# out_role.net
KiCad netlist of a schematic drawn in Altium Designer
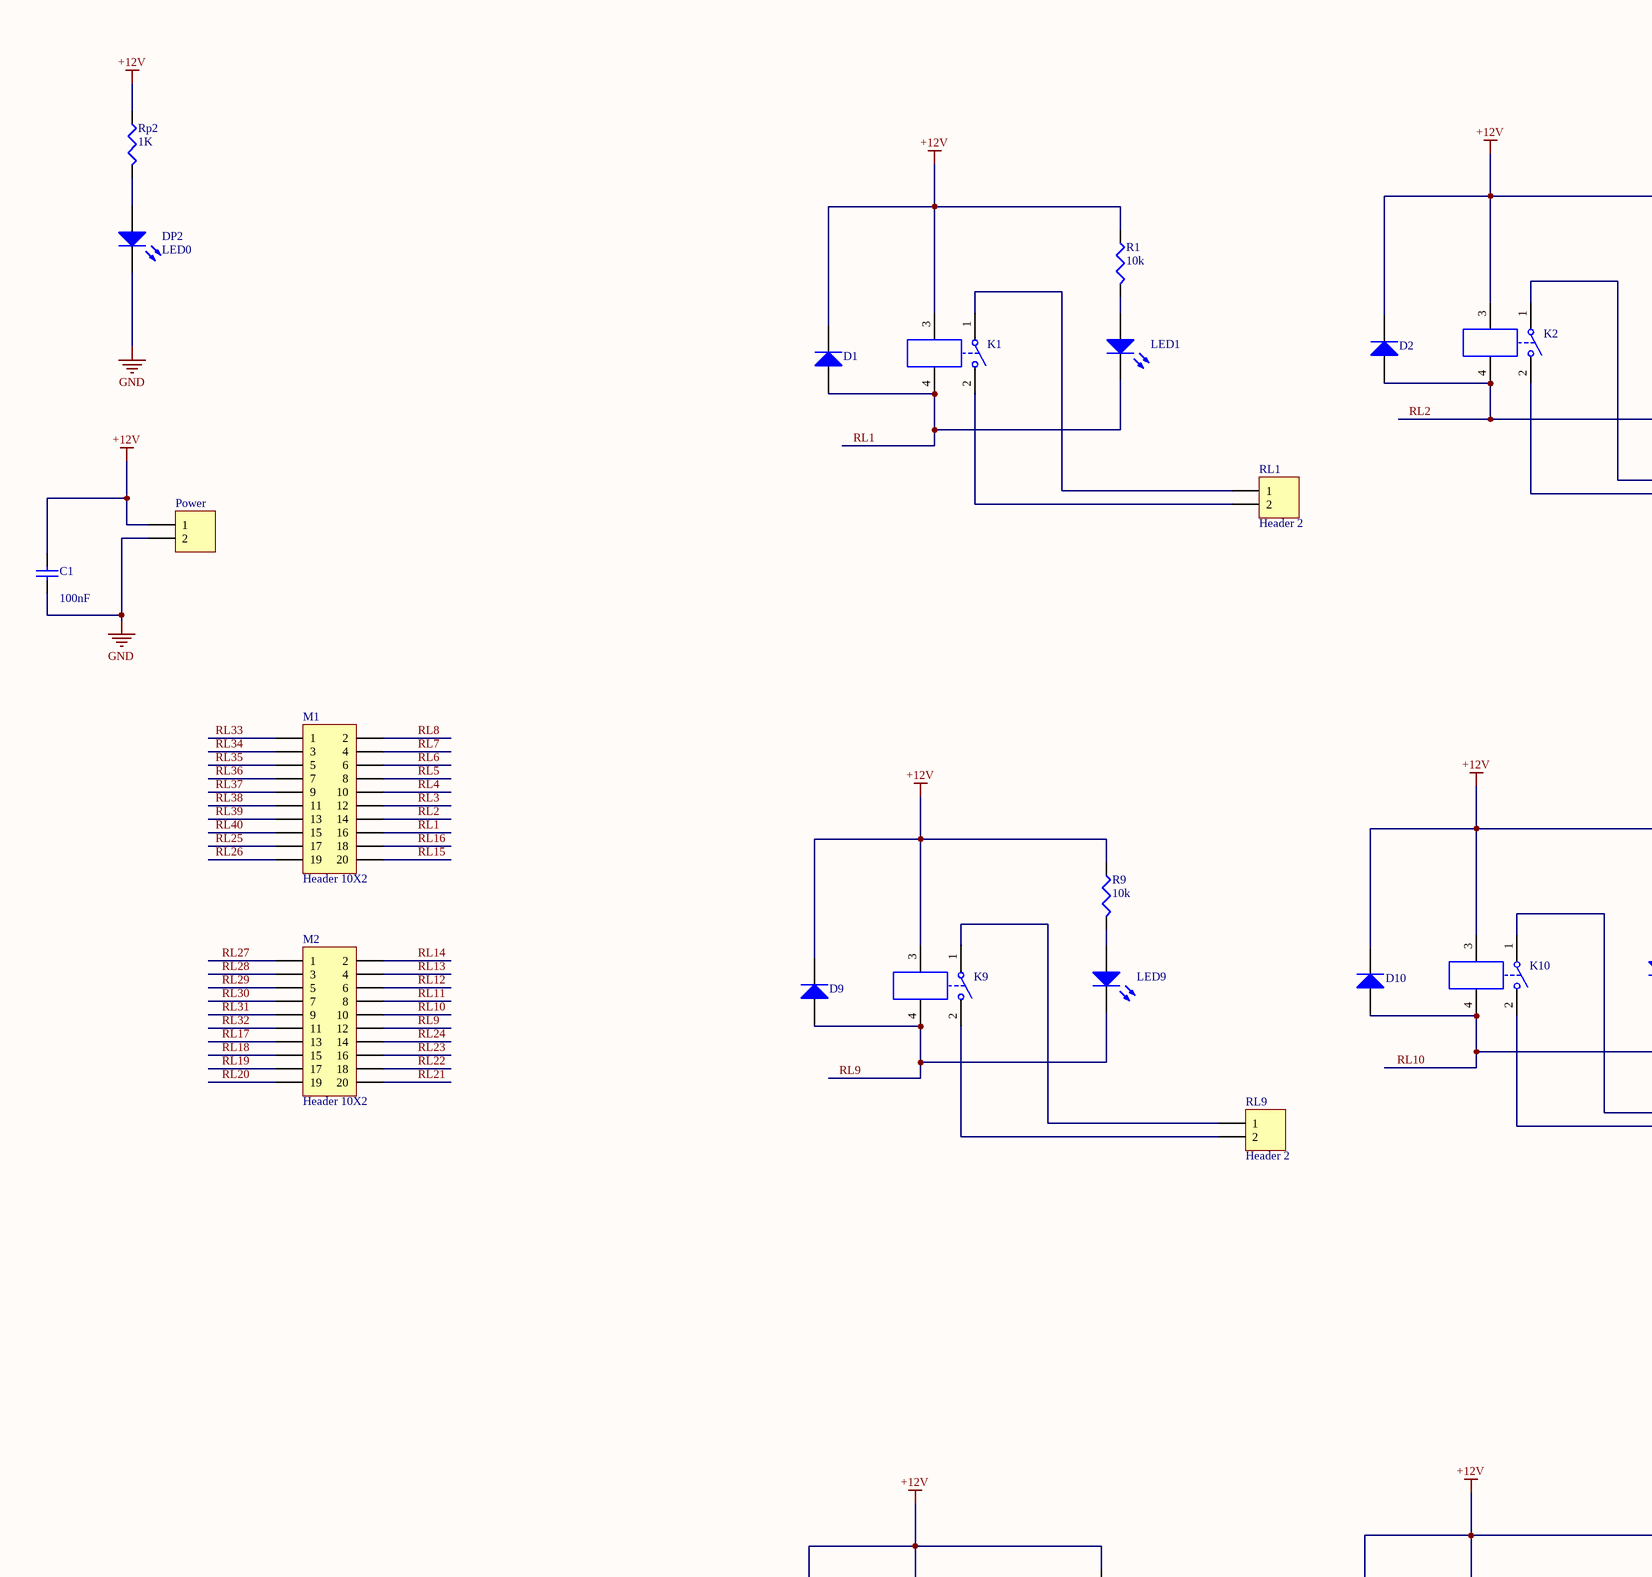
[diagram p0: out_role.SchDoc, top left]
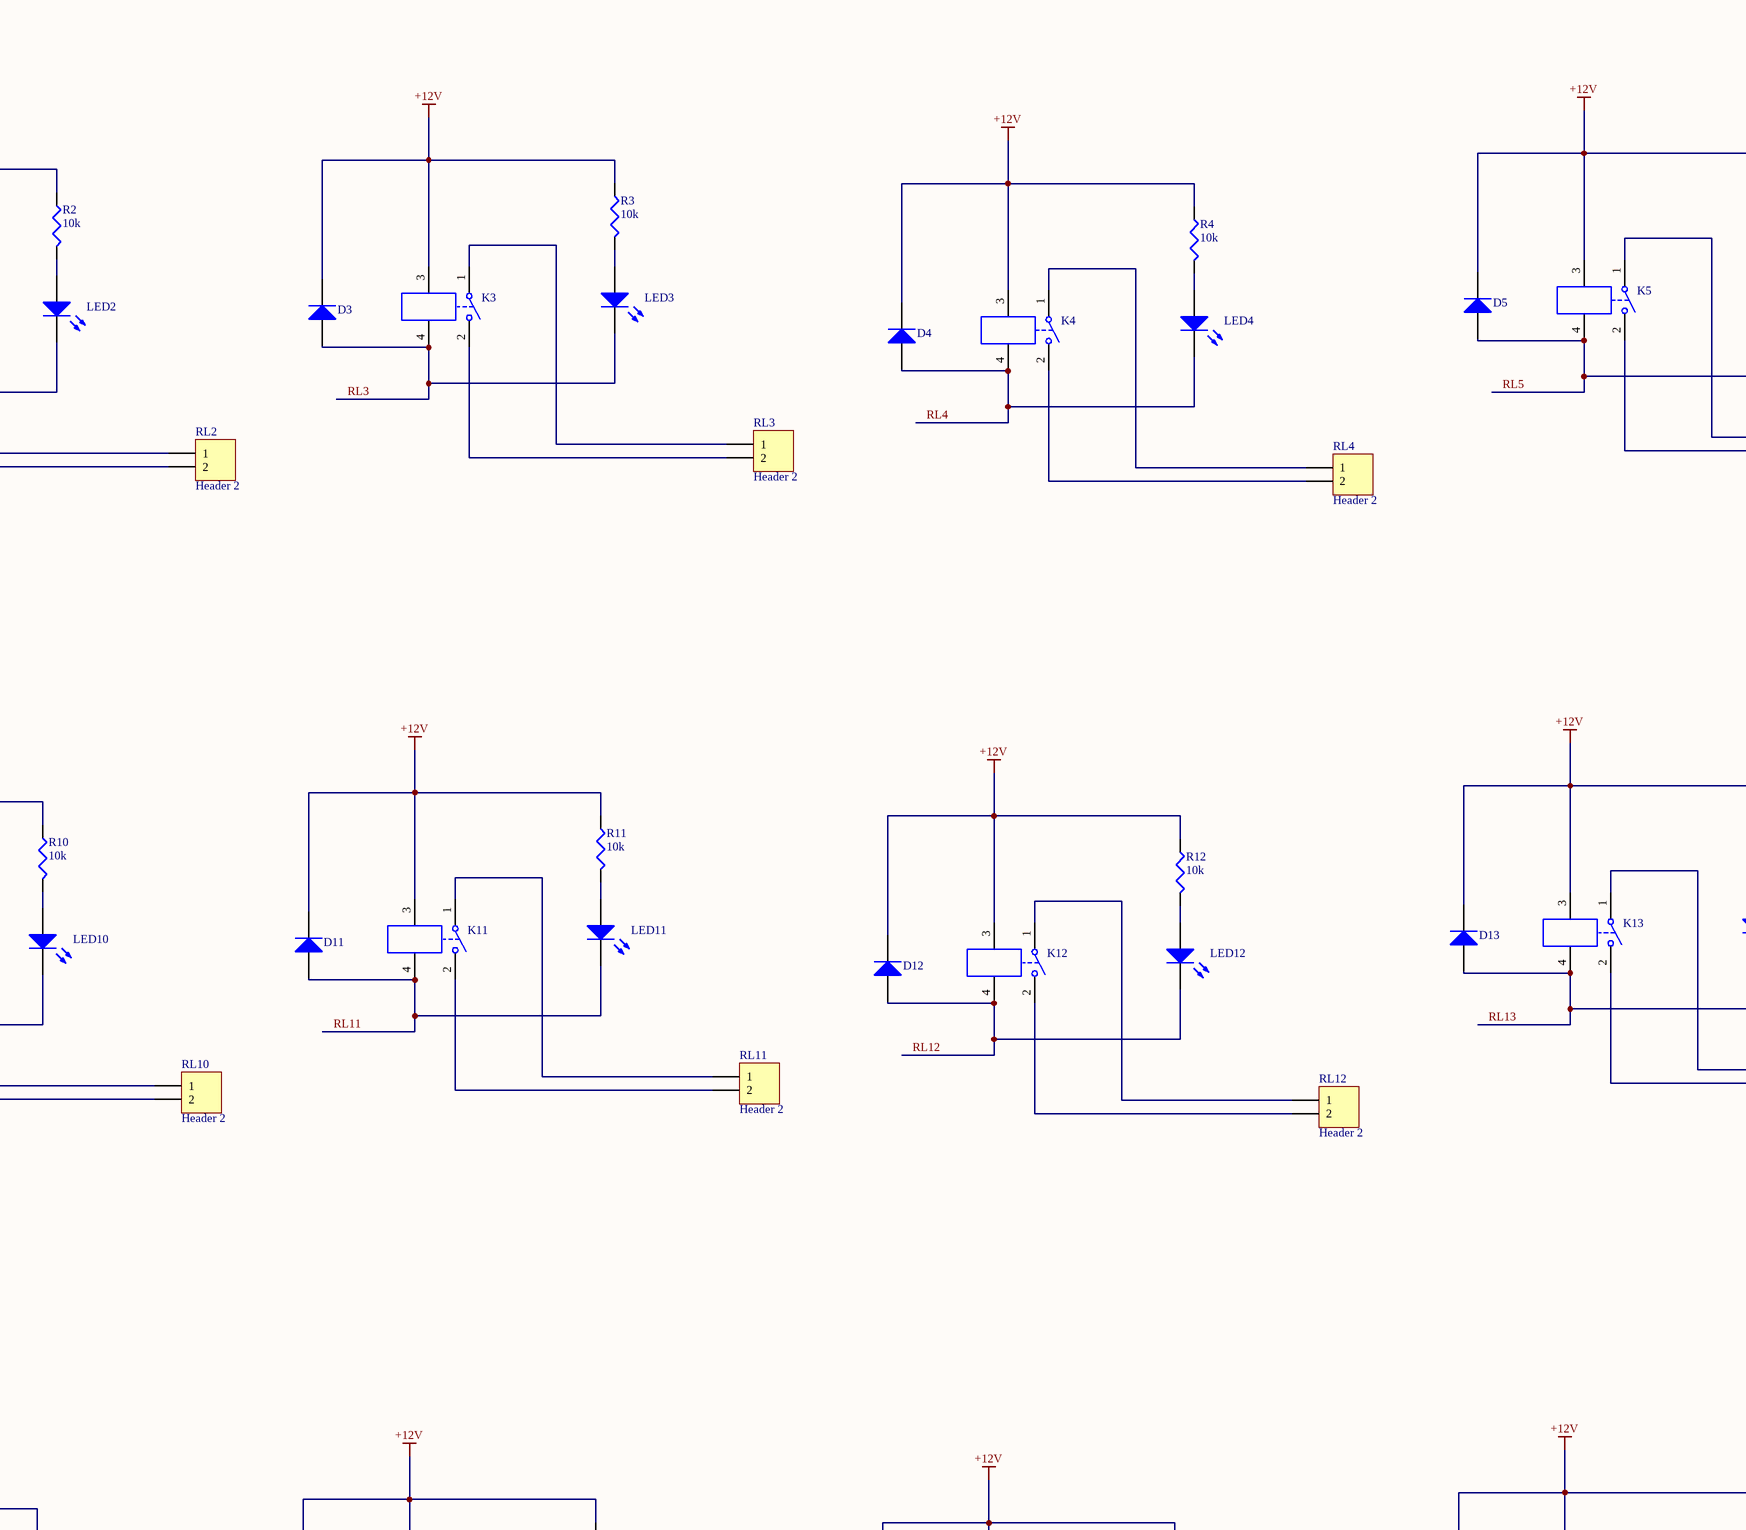
[diagram p1: out_role.SchDoc, top middle]
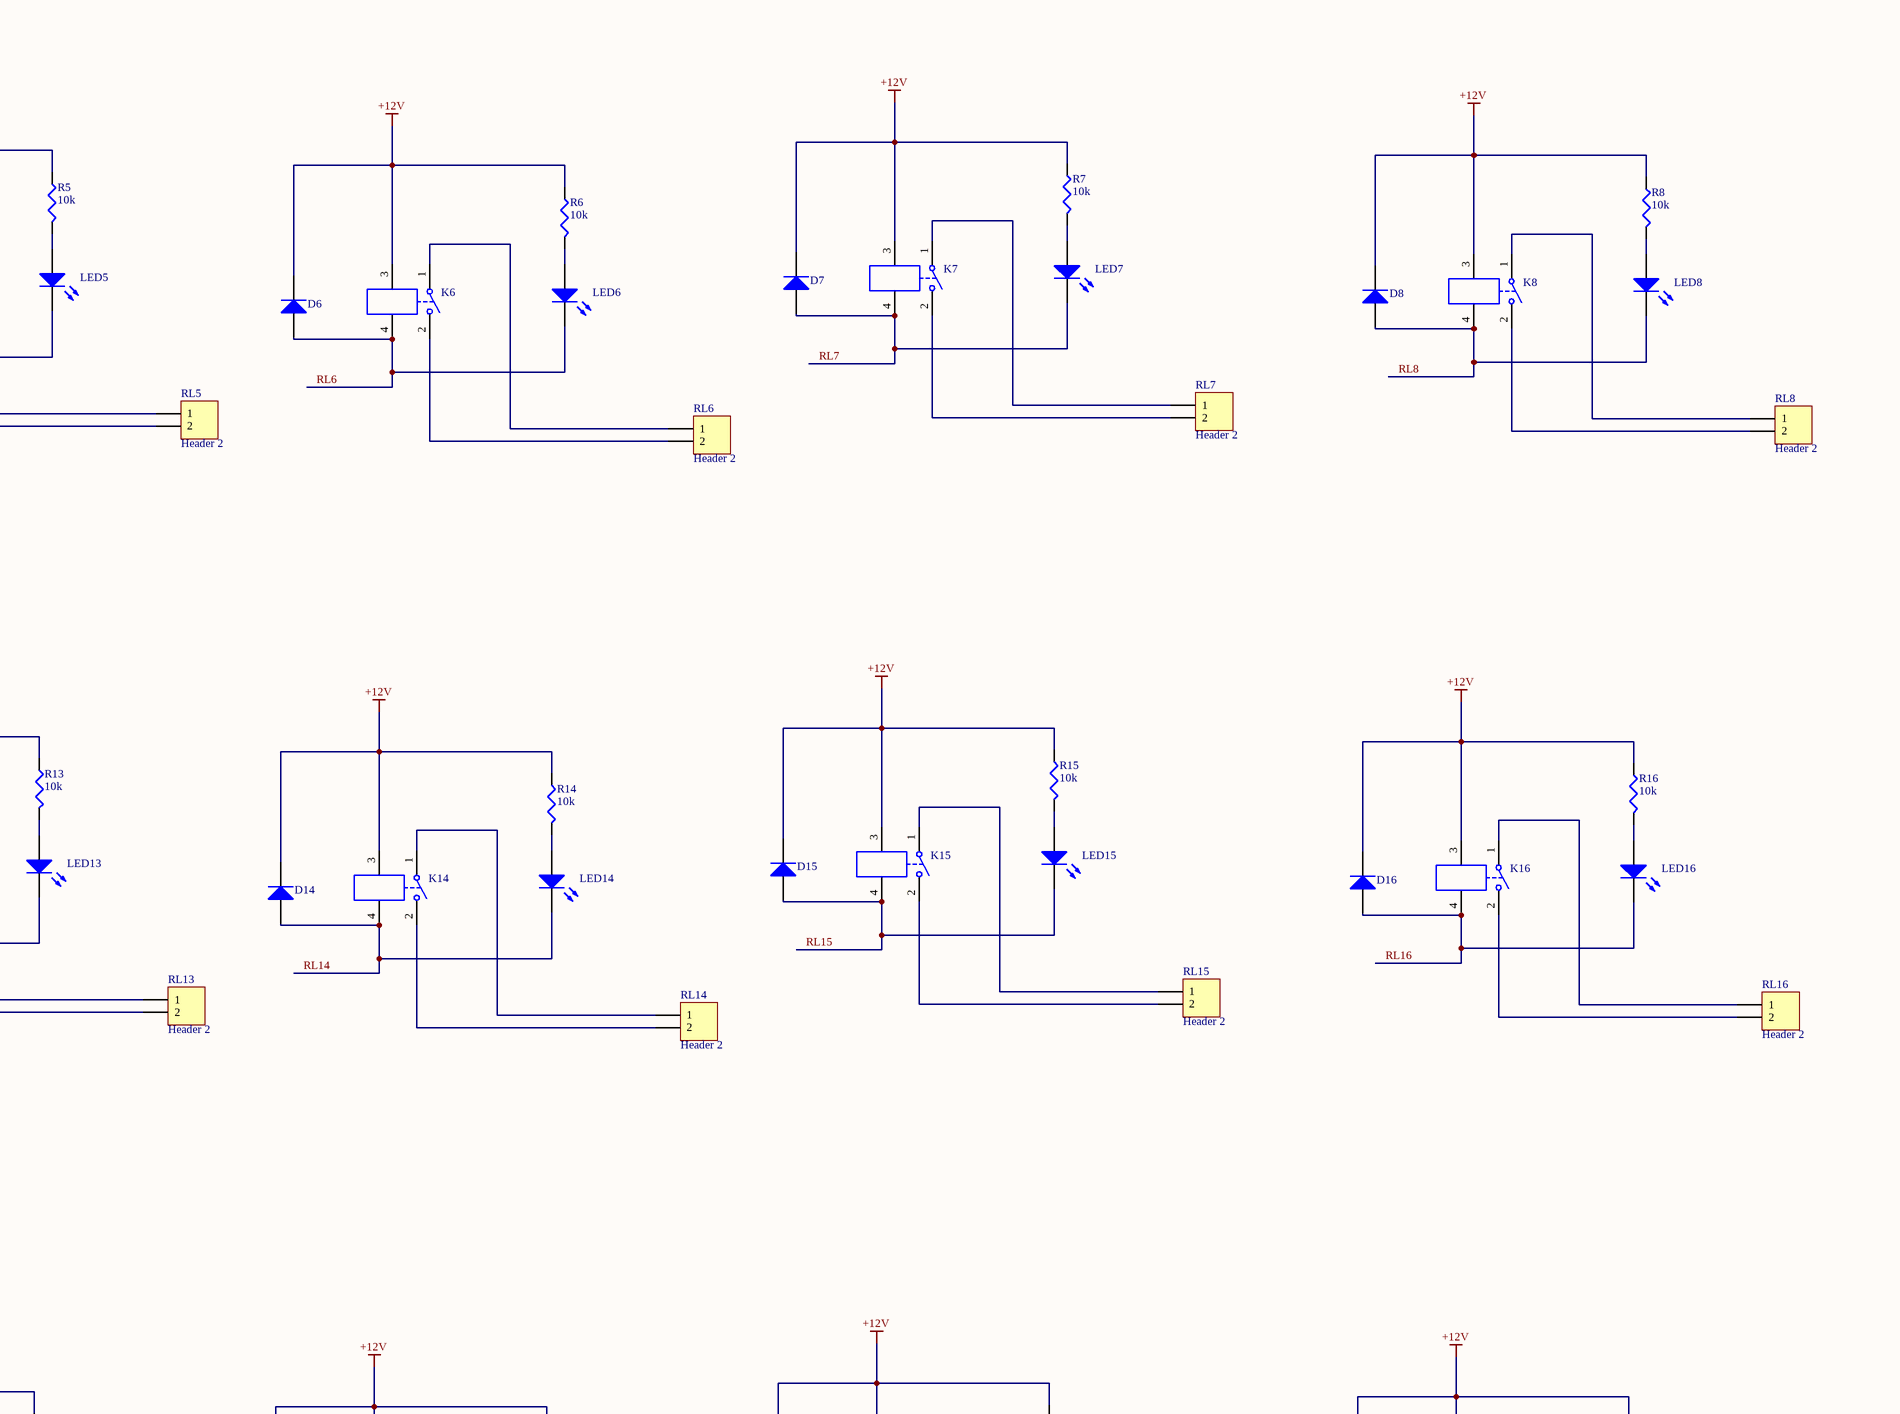
[diagram p2: out_role.SchDoc, top right]
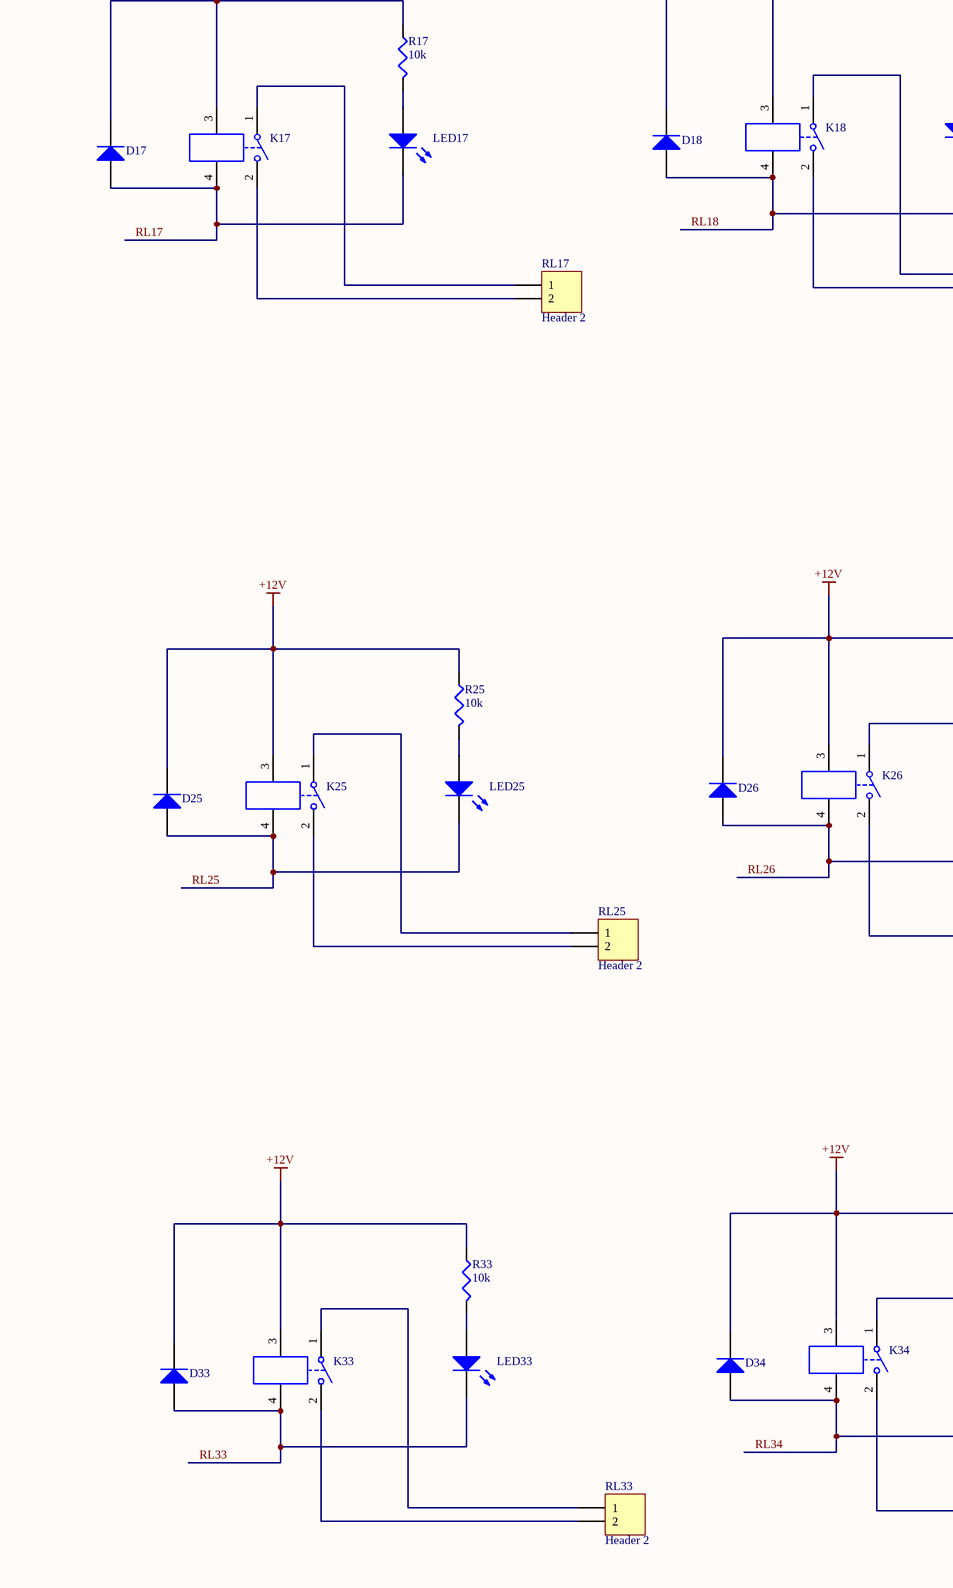
[diagram p3: out_role.SchDoc, bottom left]
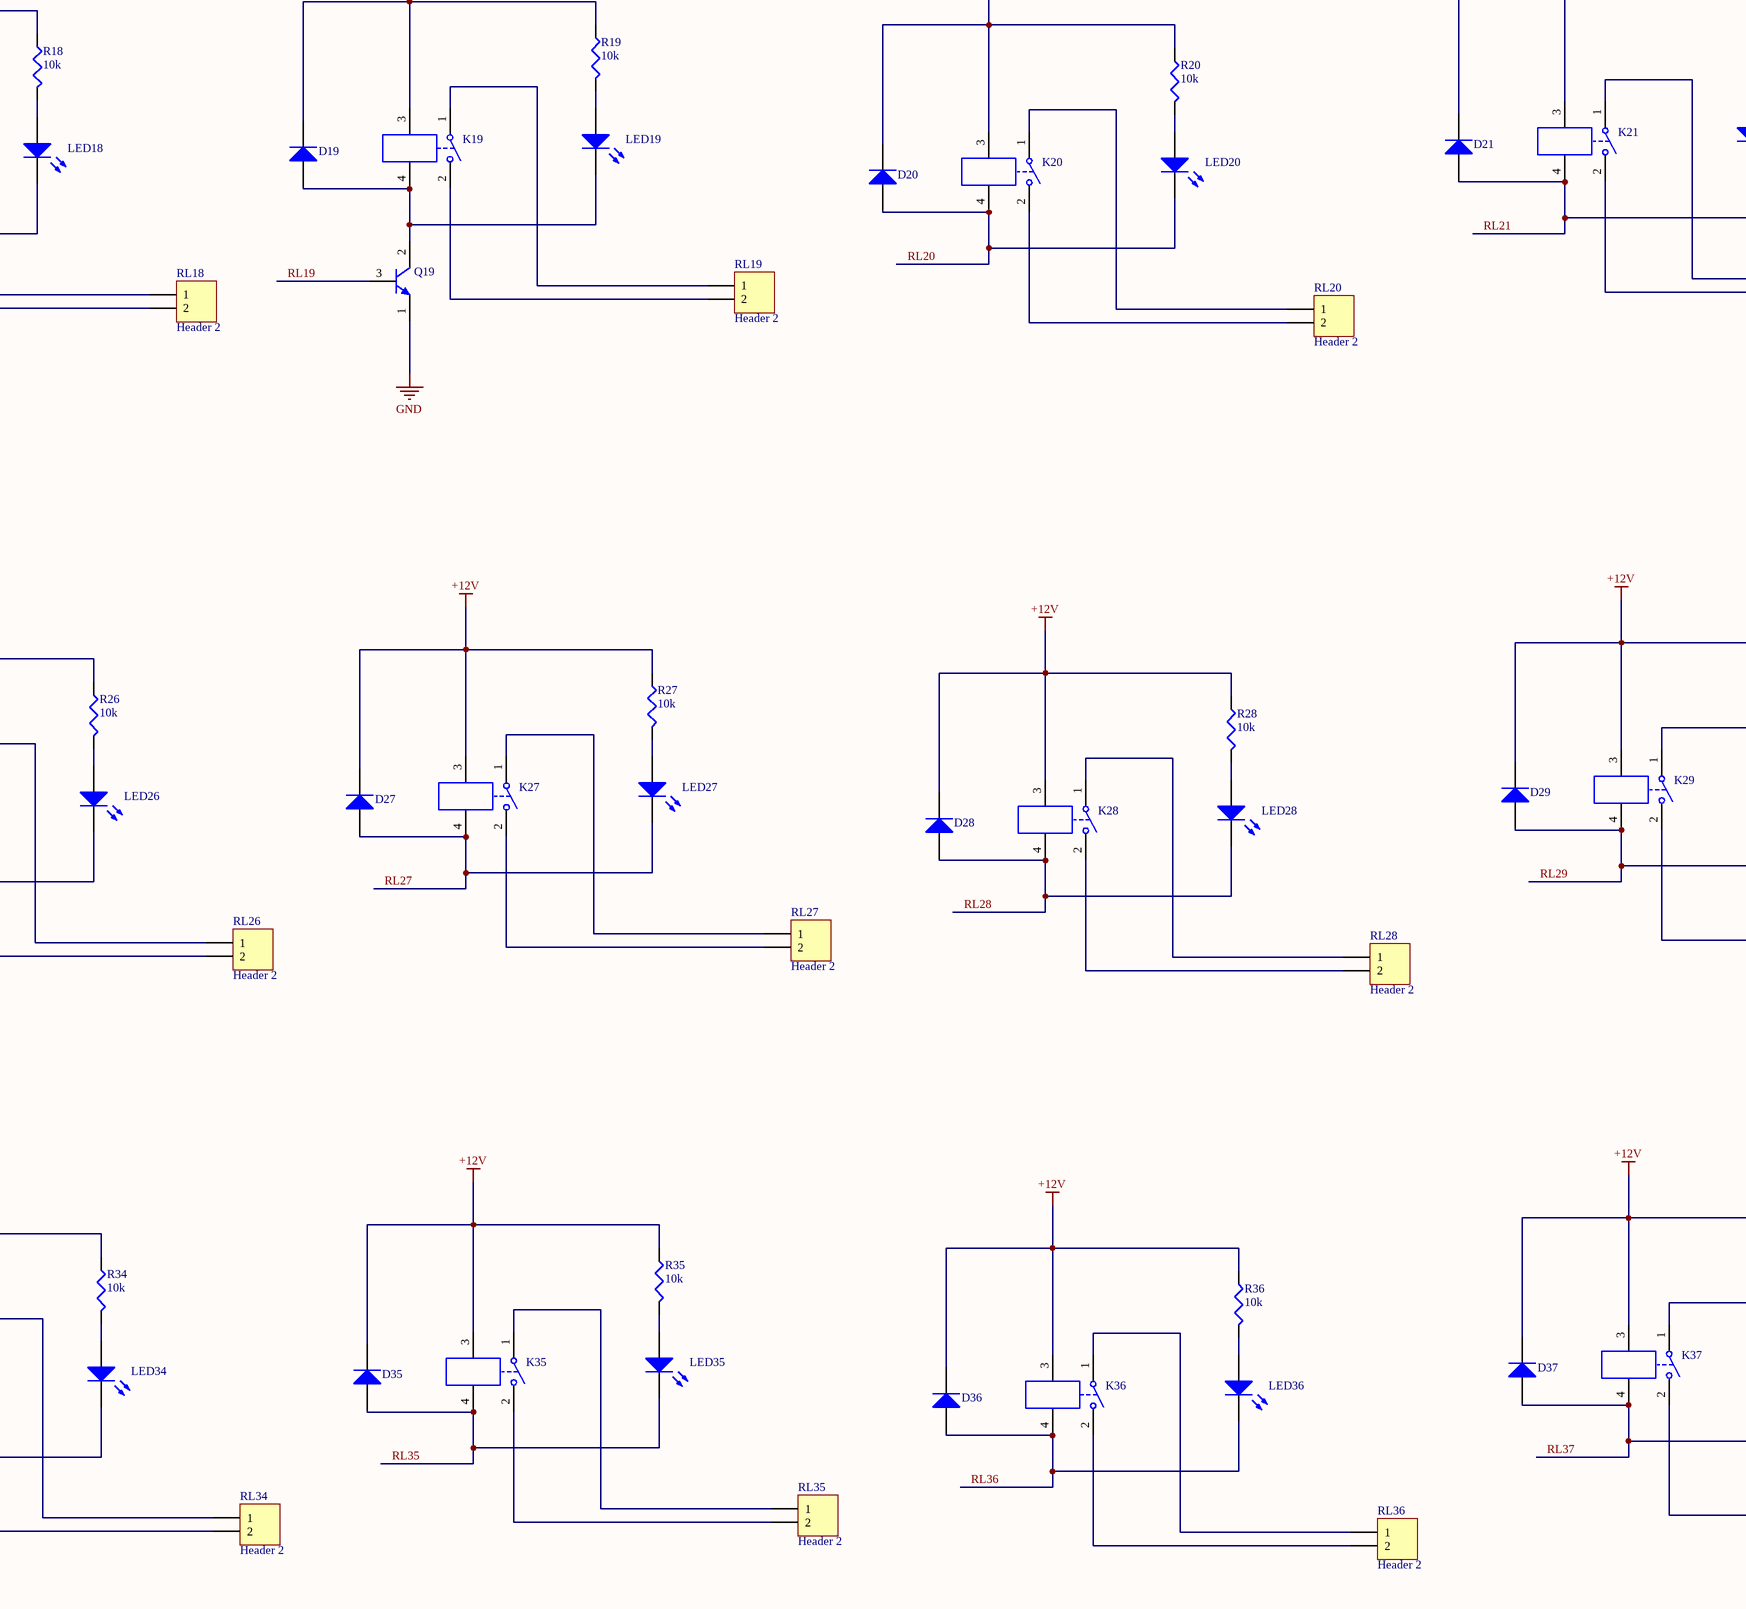
[diagram p4: out_role.SchDoc, bottom middle]
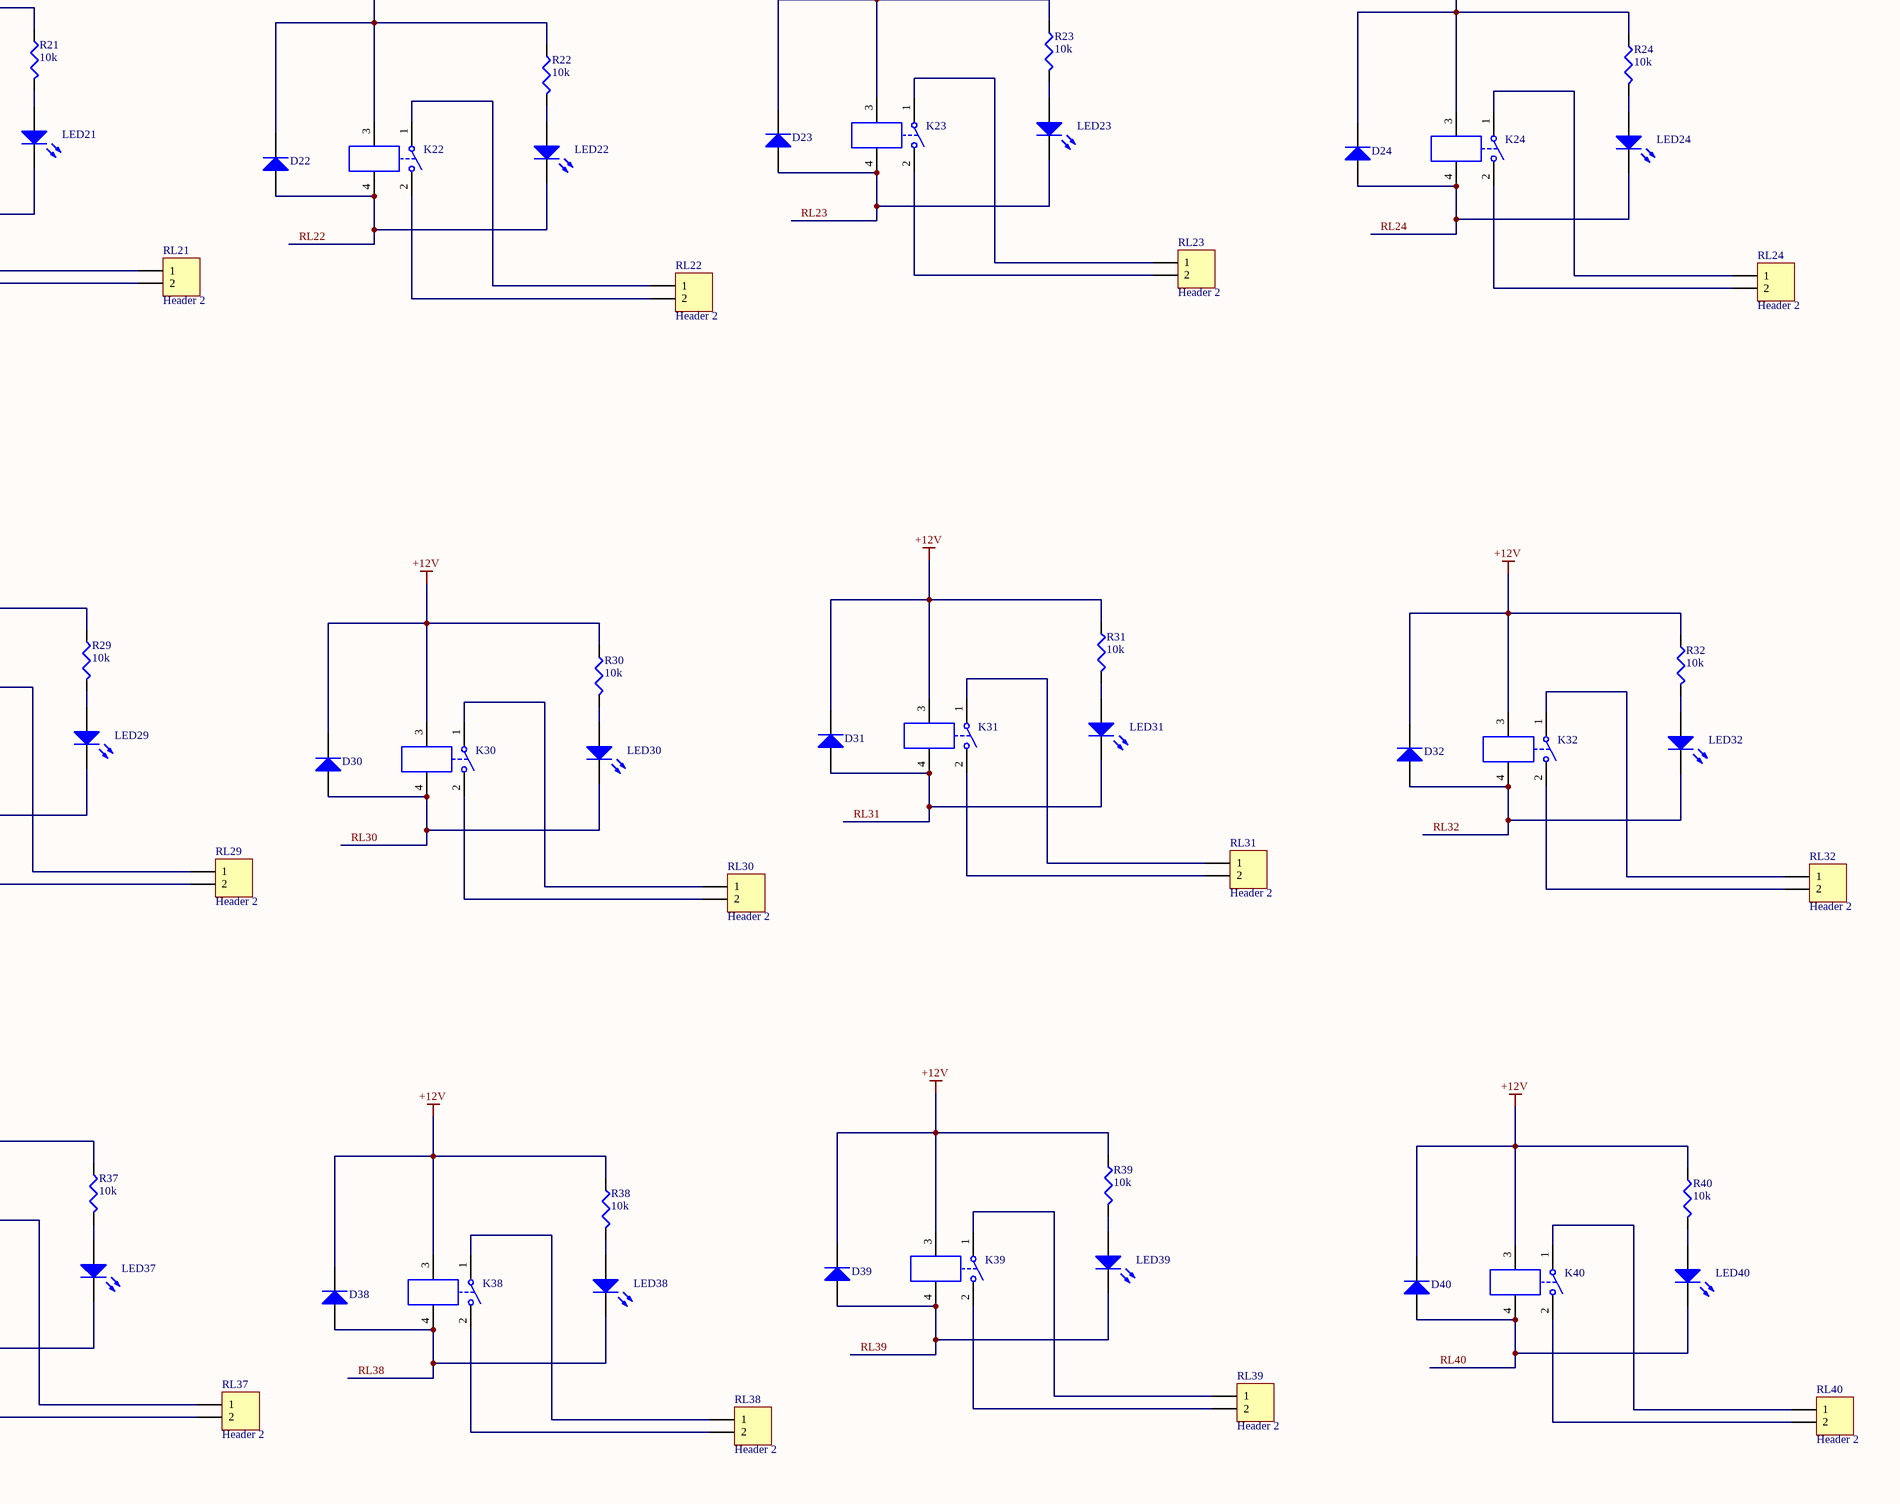
[diagram p5: out_role.SchDoc, bottom right]

(export (version "E")
  (design (tool "Eeschema 10.0.6"))
  (components
    (comp (ref "C1")
      (value "100nF")
      (footprint "Device:tu_gom")
      (description "Capacitor")
      (fields (field (name "Comment") "Cap") (field (name "PUBLISHER") "Altium Limited"))
      (libsource (lib "Miscellaneous Devices") (part "Cap"))
    )
    (comp (ref "D1")
      (value "Diode")
      (footprint "Device:D_1A")
      (description "Default Diode")
      (fields (field (name "PUBLISHER") "Altium Limited"))
      (libsource (lib "Miscellaneous Devices") (part "Diode"))
    )
    (comp (ref "D2")
      (value "Diode")
      (footprint "Device:D_1A")
      (description "Default Diode")
      (fields (field (name "PUBLISHER") "Altium Limited"))
      (libsource (lib "Miscellaneous Devices") (part "Diode"))
    )
    (comp (ref "D3")
      (value "Diode")
      (footprint "Device:D_1A")
      (description "Default Diode")
      (fields (field (name "PUBLISHER") "Altium Limited"))
      (libsource (lib "Miscellaneous Devices") (part "Diode"))
    )
    (comp (ref "D4")
      (value "Diode")
      (footprint "Device:D_1A")
      (description "Default Diode")
      (fields (field (name "PUBLISHER") "Altium Limited"))
      (libsource (lib "Miscellaneous Devices") (part "Diode"))
    )
    (comp (ref "D5")
      (value "Diode")
      (footprint "Device:D_1A")
      (description "Default Diode")
      (fields (field (name "PUBLISHER") "Altium Limited"))
      (libsource (lib "Miscellaneous Devices") (part "Diode"))
    )
    (comp (ref "D6")
      (value "Diode")
      (footprint "Device:D_1A")
      (description "Default Diode")
      (fields (field (name "PUBLISHER") "Altium Limited"))
      (libsource (lib "Miscellaneous Devices") (part "Diode"))
    )
    (comp (ref "D7")
      (value "Diode")
      (footprint "Device:D_1A")
      (description "Default Diode")
      (fields (field (name "PUBLISHER") "Altium Limited"))
      (libsource (lib "Miscellaneous Devices") (part "Diode"))
    )
    (comp (ref "D8")
      (value "Diode")
      (footprint "Device:D_1A")
      (description "Default Diode")
      (fields (field (name "PUBLISHER") "Altium Limited"))
      (libsource (lib "Miscellaneous Devices") (part "Diode"))
    )
    (comp (ref "D9")
      (value "Diode")
      (footprint "Device:D_1A")
      (description "Default Diode")
      (fields (field (name "PUBLISHER") "Altium Limited"))
      (libsource (lib "Miscellaneous Devices") (part "Diode"))
    )
    (comp (ref "D10")
      (value "Diode")
      (footprint "Device:D_1A")
      (description "Default Diode")
      (fields (field (name "PUBLISHER") "Altium Limited"))
      (libsource (lib "Miscellaneous Devices") (part "Diode"))
    )
    (comp (ref "D11")
      (value "Diode")
      (footprint "Device:D_1A")
      (description "Default Diode")
      (fields (field (name "PUBLISHER") "Altium Limited"))
      (libsource (lib "Miscellaneous Devices") (part "Diode"))
    )
    (comp (ref "D12")
      (value "Diode")
      (footprint "Device:D_1A")
      (description "Default Diode")
      (fields (field (name "PUBLISHER") "Altium Limited"))
      (libsource (lib "Miscellaneous Devices") (part "Diode"))
    )
    (comp (ref "D13")
      (value "Diode")
      (footprint "Device:D_1A")
      (description "Default Diode")
      (fields (field (name "PUBLISHER") "Altium Limited"))
      (libsource (lib "Miscellaneous Devices") (part "Diode"))
    )
    (comp (ref "D14")
      (value "Diode")
      (footprint "Device:D_1A")
      (description "Default Diode")
      (fields (field (name "PUBLISHER") "Altium Limited"))
      (libsource (lib "Miscellaneous Devices") (part "Diode"))
    )
    (comp (ref "D15")
      (value "Diode")
      (footprint "Device:D_1A")
      (description "Default Diode")
      (fields (field (name "PUBLISHER") "Altium Limited"))
      (libsource (lib "Miscellaneous Devices") (part "Diode"))
    )
    (comp (ref "D16")
      (value "Diode")
      (footprint "Device:D_1A")
      (description "Default Diode")
      (fields (field (name "PUBLISHER") "Altium Limited"))
      (libsource (lib "Miscellaneous Devices") (part "Diode"))
    )
    (comp (ref "D17")
      (value "Diode")
      (footprint "Device:D_1A")
      (description "Default Diode")
      (fields (field (name "PUBLISHER") "Altium Limited"))
      (libsource (lib "Miscellaneous Devices") (part "Diode"))
    )
    (comp (ref "D18")
      (value "Diode")
      (footprint "Device:D_1A")
      (description "Default Diode")
      (fields (field (name "PUBLISHER") "Altium Limited"))
      (libsource (lib "Miscellaneous Devices") (part "Diode"))
    )
    (comp (ref "D19")
      (value "Diode")
      (footprint "Device:D_1A")
      (description "Default Diode")
      (fields (field (name "PUBLISHER") "Altium Limited"))
      (libsource (lib "Miscellaneous Devices") (part "Diode"))
    )
    (comp (ref "D20")
      (value "Diode")
      (footprint "Device:D_1A")
      (description "Default Diode")
      (fields (field (name "PUBLISHER") "Altium Limited"))
      (libsource (lib "Miscellaneous Devices") (part "Diode"))
    )
    (comp (ref "D21")
      (value "Diode")
      (footprint "Device:D_1A")
      (description "Default Diode")
      (fields (field (name "PUBLISHER") "Altium Limited"))
      (libsource (lib "Miscellaneous Devices") (part "Diode"))
    )
    (comp (ref "D22")
      (value "Diode")
      (footprint "Device:D_1A")
      (description "Default Diode")
      (fields (field (name "PUBLISHER") "Altium Limited"))
      (libsource (lib "Miscellaneous Devices") (part "Diode"))
    )
    (comp (ref "D23")
      (value "Diode")
      (footprint "Device:D_1A")
      (description "Default Diode")
      (fields (field (name "PUBLISHER") "Altium Limited"))
      (libsource (lib "Miscellaneous Devices") (part "Diode"))
    )
    (comp (ref "D24")
      (value "Diode")
      (footprint "Device:D_1A")
      (description "Default Diode")
      (fields (field (name "PUBLISHER") "Altium Limited"))
      (libsource (lib "Miscellaneous Devices") (part "Diode"))
    )
    (comp (ref "D25")
      (value "Diode")
      (footprint "Device:D_1A")
      (description "Default Diode")
      (fields (field (name "PUBLISHER") "Altium Limited"))
      (libsource (lib "Miscellaneous Devices") (part "Diode"))
    )
    (comp (ref "D26")
      (value "Diode")
      (footprint "Device:D_1A")
      (description "Default Diode")
      (fields (field (name "PUBLISHER") "Altium Limited"))
      (libsource (lib "Miscellaneous Devices") (part "Diode"))
    )
    (comp (ref "D27")
      (value "Diode")
      (footprint "Device:D_1A")
      (description "Default Diode")
      (fields (field (name "PUBLISHER") "Altium Limited"))
      (libsource (lib "Miscellaneous Devices") (part "Diode"))
    )
    (comp (ref "D28")
      (value "Diode")
      (footprint "Device:D_1A")
      (description "Default Diode")
      (fields (field (name "PUBLISHER") "Altium Limited"))
      (libsource (lib "Miscellaneous Devices") (part "Diode"))
    )
    (comp (ref "D29")
      (value "Diode")
      (footprint "Device:D_1A")
      (description "Default Diode")
      (fields (field (name "PUBLISHER") "Altium Limited"))
      (libsource (lib "Miscellaneous Devices") (part "Diode"))
    )
    (comp (ref "D30")
      (value "Diode")
      (footprint "Device:D_1A")
      (description "Default Diode")
      (fields (field (name "PUBLISHER") "Altium Limited"))
      (libsource (lib "Miscellaneous Devices") (part "Diode"))
    )
    (comp (ref "D31")
      (value "Diode")
      (footprint "Device:D_1A")
      (description "Default Diode")
      (fields (field (name "PUBLISHER") "Altium Limited"))
      (libsource (lib "Miscellaneous Devices") (part "Diode"))
    )
    (comp (ref "D32")
      (value "Diode")
      (footprint "Device:D_1A")
      (description "Default Diode")
      (fields (field (name "PUBLISHER") "Altium Limited"))
      (libsource (lib "Miscellaneous Devices") (part "Diode"))
    )
    (comp (ref "D33")
      (value "Diode")
      (footprint "Device:D_1A")
      (description "Default Diode")
      (fields (field (name "PUBLISHER") "Altium Limited"))
      (libsource (lib "Miscellaneous Devices") (part "Diode"))
    )
    (comp (ref "D34")
      (value "Diode")
      (footprint "Device:D_1A")
      (description "Default Diode")
      (fields (field (name "PUBLISHER") "Altium Limited"))
      (libsource (lib "Miscellaneous Devices") (part "Diode"))
    )
    (comp (ref "D35")
      (value "Diode")
      (footprint "Device:D_1A")
      (description "Default Diode")
      (fields (field (name "PUBLISHER") "Altium Limited"))
      (libsource (lib "Miscellaneous Devices") (part "Diode"))
    )
    (comp (ref "D36")
      (value "Diode")
      (footprint "Device:D_1A")
      (description "Default Diode")
      (fields (field (name "PUBLISHER") "Altium Limited"))
      (libsource (lib "Miscellaneous Devices") (part "Diode"))
    )
    (comp (ref "D37")
      (value "Diode")
      (footprint "Device:D_1A")
      (description "Default Diode")
      (fields (field (name "PUBLISHER") "Altium Limited"))
      (libsource (lib "Miscellaneous Devices") (part "Diode"))
    )
    (comp (ref "D38")
      (value "Diode")
      (footprint "Device:D_1A")
      (description "Default Diode")
      (fields (field (name "PUBLISHER") "Altium Limited"))
      (libsource (lib "Miscellaneous Devices") (part "Diode"))
    )
    (comp (ref "D39")
      (value "Diode")
      (footprint "Device:D_1A")
      (description "Default Diode")
      (fields (field (name "PUBLISHER") "Altium Limited"))
      (libsource (lib "Miscellaneous Devices") (part "Diode"))
    )
    (comp (ref "D40")
      (value "Diode")
      (footprint "Device:D_1A")
      (description "Default Diode")
      (fields (field (name "PUBLISHER") "Altium Limited"))
      (libsource (lib "Miscellaneous Devices") (part "Diode"))
    )
    (comp (ref "DP2")
      (value "LED0")
      (footprint "Device:LED_3")
      (description "Typical INFRARED GaAs LED")
      (fields (field (name "PUBLISHER") "Altium Limited"))
      (libsource (lib "Miscellaneous Devices") (part "LED0"))
    )
    (comp (ref "K1")
      (value "Relay-SPST")
      (footprint "Device:ROLE12V_JP")
      (description "Single-Pole Single-Throw Relay")
      (fields (field (name "PUBLISHER") "Altium Limited"))
      (libsource (lib "Miscellaneous Devices") (part "Relay-SPST"))
    )
    (comp (ref "K2")
      (value "Relay-SPST")
      (footprint "Device:ROLE12V_JP")
      (description "Single-Pole Single-Throw Relay")
      (fields (field (name "PUBLISHER") "Altium Limited"))
      (libsource (lib "Miscellaneous Devices") (part "Relay-SPST"))
    )
    (comp (ref "K3")
      (value "Relay-SPST")
      (footprint "Device:ROLE12V_JP")
      (description "Single-Pole Single-Throw Relay")
      (fields (field (name "PUBLISHER") "Altium Limited"))
      (libsource (lib "Miscellaneous Devices") (part "Relay-SPST"))
    )
    (comp (ref "K4")
      (value "Relay-SPST")
      (footprint "Device:ROLE12V_JP")
      (description "Single-Pole Single-Throw Relay")
      (fields (field (name "PUBLISHER") "Altium Limited"))
      (libsource (lib "Miscellaneous Devices") (part "Relay-SPST"))
    )
    (comp (ref "K5")
      (value "Relay-SPST")
      (footprint "Device:ROLE12V_JP")
      (description "Single-Pole Single-Throw Relay")
      (fields (field (name "PUBLISHER") "Altium Limited"))
      (libsource (lib "Miscellaneous Devices") (part "Relay-SPST"))
    )
    (comp (ref "K6")
      (value "Relay-SPST")
      (footprint "Device:ROLE12V_JP")
      (description "Single-Pole Single-Throw Relay")
      (fields (field (name "PUBLISHER") "Altium Limited"))
      (libsource (lib "Miscellaneous Devices") (part "Relay-SPST"))
    )
    (comp (ref "K7")
      (value "Relay-SPST")
      (footprint "Device:ROLE12V_JP")
      (description "Single-Pole Single-Throw Relay")
      (fields (field (name "PUBLISHER") "Altium Limited"))
      (libsource (lib "Miscellaneous Devices") (part "Relay-SPST"))
    )
    (comp (ref "K8")
      (value "Relay-SPST")
      (footprint "Device:ROLE12V_JP")
      (description "Single-Pole Single-Throw Relay")
      (fields (field (name "PUBLISHER") "Altium Limited"))
      (libsource (lib "Miscellaneous Devices") (part "Relay-SPST"))
    )
    (comp (ref "K9")
      (value "Relay-SPST")
      (footprint "Device:ROLE12V_JP")
      (description "Single-Pole Single-Throw Relay")
      (fields (field (name "PUBLISHER") "Altium Limited"))
      (libsource (lib "Miscellaneous Devices") (part "Relay-SPST"))
    )
    (comp (ref "K10")
      (value "Relay-SPST")
      (footprint "Device:ROLE12V_JP")
      (description "Single-Pole Single-Throw Relay")
      (fields (field (name "PUBLISHER") "Altium Limited"))
      (libsource (lib "Miscellaneous Devices") (part "Relay-SPST"))
    )
    (comp (ref "K11")
      (value "Relay-SPST")
      (footprint "Device:ROLE12V_JP")
      (description "Single-Pole Single-Throw Relay")
      (fields (field (name "PUBLISHER") "Altium Limited"))
      (libsource (lib "Miscellaneous Devices") (part "Relay-SPST"))
    )
    (comp (ref "K12")
      (value "Relay-SPST")
      (footprint "Device:ROLE12V_JP")
      (description "Single-Pole Single-Throw Relay")
      (fields (field (name "PUBLISHER") "Altium Limited"))
      (libsource (lib "Miscellaneous Devices") (part "Relay-SPST"))
    )
    (comp (ref "K13")
      (value "Relay-SPST")
      (footprint "Device:ROLE12V_JP")
      (description "Single-Pole Single-Throw Relay")
      (fields (field (name "PUBLISHER") "Altium Limited"))
      (libsource (lib "Miscellaneous Devices") (part "Relay-SPST"))
    )
    (comp (ref "K14")
      (value "Relay-SPST")
      (footprint "Device:ROLE12V_JP")
      (description "Single-Pole Single-Throw Relay")
      (fields (field (name "PUBLISHER") "Altium Limited"))
      (libsource (lib "Miscellaneous Devices") (part "Relay-SPST"))
    )
    (comp (ref "K15")
      (value "Relay-SPST")
      (footprint "Device:ROLE12V_JP")
      (description "Single-Pole Single-Throw Relay")
      (fields (field (name "PUBLISHER") "Altium Limited"))
      (libsource (lib "Miscellaneous Devices") (part "Relay-SPST"))
    )
    (comp (ref "K16")
      (value "Relay-SPST")
      (footprint "Device:ROLE12V_JP")
      (description "Single-Pole Single-Throw Relay")
      (fields (field (name "PUBLISHER") "Altium Limited"))
      (libsource (lib "Miscellaneous Devices") (part "Relay-SPST"))
    )
    (comp (ref "K17")
      (value "Relay-SPST")
      (footprint "Device:ROLE12V_JP")
      (description "Single-Pole Single-Throw Relay")
      (fields (field (name "PUBLISHER") "Altium Limited"))
      (libsource (lib "Miscellaneous Devices") (part "Relay-SPST"))
    )
    (comp (ref "K18")
      (value "Relay-SPST")
      (footprint "Device:ROLE12V_JP")
      (description "Single-Pole Single-Throw Relay")
      (fields (field (name "PUBLISHER") "Altium Limited"))
      (libsource (lib "Miscellaneous Devices") (part "Relay-SPST"))
    )
    (comp (ref "K19")
      (value "Relay-SPST")
      (footprint "Device:ROLE12V_JP")
      (description "Single-Pole Single-Throw Relay")
      (fields (field (name "PUBLISHER") "Altium Limited"))
      (libsource (lib "Miscellaneous Devices") (part "Relay-SPST"))
    )
    (comp (ref "K20")
      (value "Relay-SPST")
      (footprint "Device:ROLE12V_JP")
      (description "Single-Pole Single-Throw Relay")
      (fields (field (name "PUBLISHER") "Altium Limited"))
      (libsource (lib "Miscellaneous Devices") (part "Relay-SPST"))
    )
    (comp (ref "K21")
      (value "Relay-SPST")
      (footprint "Device:ROLE12V_JP")
      (description "Single-Pole Single-Throw Relay")
      (fields (field (name "PUBLISHER") "Altium Limited"))
      (libsource (lib "Miscellaneous Devices") (part "Relay-SPST"))
    )
    (comp (ref "K22")
      (value "Relay-SPST")
      (footprint "Device:ROLE12V_JP")
      (description "Single-Pole Single-Throw Relay")
      (fields (field (name "PUBLISHER") "Altium Limited"))
      (libsource (lib "Miscellaneous Devices") (part "Relay-SPST"))
    )
    (comp (ref "K23")
      (value "Relay-SPST")
      (footprint "Device:ROLE12V_JP")
      (description "Single-Pole Single-Throw Relay")
      (fields (field (name "PUBLISHER") "Altium Limited"))
      (libsource (lib "Miscellaneous Devices") (part "Relay-SPST"))
    )
    (comp (ref "K24")
      (value "Relay-SPST")
      (footprint "Device:ROLE12V_JP")
      (description "Single-Pole Single-Throw Relay")
      (fields (field (name "PUBLISHER") "Altium Limited"))
      (libsource (lib "Miscellaneous Devices") (part "Relay-SPST"))
    )
    (comp (ref "K25")
      (value "Relay-SPST")
      (footprint "Device:ROLE12V_JP")
      (description "Single-Pole Single-Throw Relay")
      (fields (field (name "PUBLISHER") "Altium Limited"))
      (libsource (lib "Miscellaneous Devices") (part "Relay-SPST"))
    )
    (comp (ref "K26")
      (value "Relay-SPST")
      (footprint "Device:ROLE12V_JP")
      (description "Single-Pole Single-Throw Relay")
      (fields (field (name "PUBLISHER") "Altium Limited"))
      (libsource (lib "Miscellaneous Devices") (part "Relay-SPST"))
    )
    (comp (ref "K27")
      (value "Relay-SPST")
      (footprint "Device:ROLE12V_JP")
      (description "Single-Pole Single-Throw Relay")
      (fields (field (name "PUBLISHER") "Altium Limited"))
      (libsource (lib "Miscellaneous Devices") (part "Relay-SPST"))
    )
    (comp (ref "K28")
      (value "Relay-SPST")
      (footprint "Device:ROLE12V_JP")
      (description "Single-Pole Single-Throw Relay")
      (fields (field (name "PUBLISHER") "Altium Limited"))
      (libsource (lib "Miscellaneous Devices") (part "Relay-SPST"))
    )
    (comp (ref "K29")
      (value "Relay-SPST")
      (footprint "Device:ROLE12V_JP")
      (description "Single-Pole Single-Throw Relay")
      (fields (field (name "PUBLISHER") "Altium Limited"))
      (libsource (lib "Miscellaneous Devices") (part "Relay-SPST"))
    )
    (comp (ref "K30")
      (value "Relay-SPST")
      (footprint "Device:ROLE12V_JP")
      (description "Single-Pole Single-Throw Relay")
      (fields (field (name "PUBLISHER") "Altium Limited"))
      (libsource (lib "Miscellaneous Devices") (part "Relay-SPST"))
    )
    (comp (ref "K31")
      (value "Relay-SPST")
      (footprint "Device:ROLE12V_JP")
      (description "Single-Pole Single-Throw Relay")
      (fields (field (name "PUBLISHER") "Altium Limited"))
      (libsource (lib "Miscellaneous Devices") (part "Relay-SPST"))
    )
    (comp (ref "K32")
      (value "Relay-SPST")
      (footprint "Device:ROLE12V_JP")
      (description "Single-Pole Single-Throw Relay")
      (fields (field (name "PUBLISHER") "Altium Limited"))
      (libsource (lib "Miscellaneous Devices") (part "Relay-SPST"))
    )
    (comp (ref "K33")
      (value "Relay-SPST")
      (footprint "Device:ROLE12V_JP")
      (description "Single-Pole Single-Throw Relay")
      (fields (field (name "PUBLISHER") "Altium Limited"))
      (libsource (lib "Miscellaneous Devices") (part "Relay-SPST"))
    )
    (comp (ref "K34")
      (value "Relay-SPST")
      (footprint "Device:ROLE12V_JP")
      (description "Single-Pole Single-Throw Relay")
      (fields (field (name "PUBLISHER") "Altium Limited"))
      (libsource (lib "Miscellaneous Devices") (part "Relay-SPST"))
    )
    (comp (ref "K35")
      (value "Relay-SPST")
      (footprint "Device:ROLE12V_JP")
      (description "Single-Pole Single-Throw Relay")
      (fields (field (name "PUBLISHER") "Altium Limited"))
      (libsource (lib "Miscellaneous Devices") (part "Relay-SPST"))
    )
    (comp (ref "K36")
      (value "Relay-SPST")
      (footprint "Device:ROLE12V_JP")
      (description "Single-Pole Single-Throw Relay")
      (fields (field (name "PUBLISHER") "Altium Limited"))
      (libsource (lib "Miscellaneous Devices") (part "Relay-SPST"))
    )
    (comp (ref "K37")
      (value "Relay-SPST")
      (footprint "Device:ROLE12V_JP")
      (description "Single-Pole Single-Throw Relay")
      (fields (field (name "PUBLISHER") "Altium Limited"))
      (libsource (lib "Miscellaneous Devices") (part "Relay-SPST"))
    )
    (comp (ref "K38")
      (value "Relay-SPST")
      (footprint "Device:ROLE12V_JP")
      (description "Single-Pole Single-Throw Relay")
      (fields (field (name "PUBLISHER") "Altium Limited"))
      (libsource (lib "Miscellaneous Devices") (part "Relay-SPST"))
    )
    (comp (ref "K39")
      (value "Relay-SPST")
      (footprint "Device:ROLE12V_JP")
      (description "Single-Pole Single-Throw Relay")
      (fields (field (name "PUBLISHER") "Altium Limited"))
      (libsource (lib "Miscellaneous Devices") (part "Relay-SPST"))
    )
    (comp (ref "K40")
      (value "Relay-SPST")
      (footprint "Device:ROLE12V_JP")
      (description "Single-Pole Single-Throw Relay")
      (fields (field (name "PUBLISHER") "Altium Limited"))
      (libsource (lib "Miscellaneous Devices") (part "Relay-SPST"))
    )
    (comp (ref "LED1")
      (value "LED0")
      (footprint "Device:LED_3")
      (description "Typical INFRARED GaAs LED")
      (fields (field (name "PUBLISHER") "Altium Limited"))
      (libsource (lib "Miscellaneous Devices") (part "LED0"))
    )
    (comp (ref "LED2")
      (value "LED0")
      (footprint "Device:LED_3")
      (description "Typical INFRARED GaAs LED")
      (fields (field (name "PUBLISHER") "Altium Limited"))
      (libsource (lib "Miscellaneous Devices") (part "LED0"))
    )
    (comp (ref "LED3")
      (value "LED0")
      (footprint "Device:LED_3")
      (description "Typical INFRARED GaAs LED")
      (fields (field (name "PUBLISHER") "Altium Limited"))
      (libsource (lib "Miscellaneous Devices") (part "LED0"))
    )
    (comp (ref "LED4")
      (value "LED0")
      (footprint "Device:LED_3")
      (description "Typical INFRARED GaAs LED")
      (fields (field (name "PUBLISHER") "Altium Limited"))
      (libsource (lib "Miscellaneous Devices") (part "LED0"))
    )
    (comp (ref "LED5")
      (value "LED0")
      (footprint "Device:LED_3")
      (description "Typical INFRARED GaAs LED")
      (fields (field (name "PUBLISHER") "Altium Limited"))
      (libsource (lib "Miscellaneous Devices") (part "LED0"))
    )
    (comp (ref "LED6")
      (value "LED0")
      (footprint "Device:LED_3")
      (description "Typical INFRARED GaAs LED")
      (fields (field (name "PUBLISHER") "Altium Limited"))
      (libsource (lib "Miscellaneous Devices") (part "LED0"))
    )
    (comp (ref "LED7")
      (value "LED0")
      (footprint "Device:LED_3")
      (description "Typical INFRARED GaAs LED")
      (fields (field (name "PUBLISHER") "Altium Limited"))
      (libsource (lib "Miscellaneous Devices") (part "LED0"))
    )
    (comp (ref "LED8")
      (value "LED0")
      (footprint "Device:LED_3")
      (description "Typical INFRARED GaAs LED")
      (fields (field (name "PUBLISHER") "Altium Limited"))
      (libsource (lib "Miscellaneous Devices") (part "LED0"))
    )
    (comp (ref "LED9")
      (value "LED0")
      (footprint "Device:LED_3")
      (description "Typical INFRARED GaAs LED")
      (fields (field (name "PUBLISHER") "Altium Limited"))
      (libsource (lib "Miscellaneous Devices") (part "LED0"))
    )
    (comp (ref "LED10")
      (value "LED0")
      (footprint "Device:LED_3")
      (description "Typical INFRARED GaAs LED")
      (fields (field (name "PUBLISHER") "Altium Limited"))
      (libsource (lib "Miscellaneous Devices") (part "LED0"))
    )
    (comp (ref "LED11")
      (value "LED0")
      (footprint "Device:LED_3")
      (description "Typical INFRARED GaAs LED")
      (fields (field (name "PUBLISHER") "Altium Limited"))
      (libsource (lib "Miscellaneous Devices") (part "LED0"))
    )
    (comp (ref "LED12")
      (value "LED0")
      (footprint "Device:LED_3")
      (description "Typical INFRARED GaAs LED")
      (fields (field (name "PUBLISHER") "Altium Limited"))
      (libsource (lib "Miscellaneous Devices") (part "LED0"))
    )
    (comp (ref "LED13")
      (value "LED0")
      (footprint "Device:LED_3")
      (description "Typical INFRARED GaAs LED")
      (fields (field (name "PUBLISHER") "Altium Limited"))
      (libsource (lib "Miscellaneous Devices") (part "LED0"))
    )
    (comp (ref "LED14")
      (value "LED0")
      (footprint "Device:LED_3")
      (description "Typical INFRARED GaAs LED")
      (fields (field (name "PUBLISHER") "Altium Limited"))
      (libsource (lib "Miscellaneous Devices") (part "LED0"))
    )
    (comp (ref "LED15")
      (value "LED0")
      (footprint "Device:LED_3")
      (description "Typical INFRARED GaAs LED")
      (fields (field (name "PUBLISHER") "Altium Limited"))
      (libsource (lib "Miscellaneous Devices") (part "LED0"))
    )
    (comp (ref "LED16")
      (value "LED0")
      (footprint "Device:LED_3")
      (description "Typical INFRARED GaAs LED")
      (fields (field (name "PUBLISHER") "Altium Limited"))
      (libsource (lib "Miscellaneous Devices") (part "LED0"))
    )
    (comp (ref "LED17")
      (value "LED0")
      (footprint "Device:LED_3")
      (description "Typical INFRARED GaAs LED")
      (fields (field (name "PUBLISHER") "Altium Limited"))
      (libsource (lib "Miscellaneous Devices") (part "LED0"))
    )
    (comp (ref "LED18")
      (value "LED0")
      (footprint "Device:LED_3")
      (description "Typical INFRARED GaAs LED")
      (fields (field (name "PUBLISHER") "Altium Limited"))
      (libsource (lib "Miscellaneous Devices") (part "LED0"))
    )
    (comp (ref "LED19")
      (value "LED0")
      (footprint "Device:LED_3")
      (description "Typical INFRARED GaAs LED")
      (fields (field (name "PUBLISHER") "Altium Limited"))
      (libsource (lib "Miscellaneous Devices") (part "LED0"))
    )
    (comp (ref "LED20")
      (value "LED0")
      (footprint "Device:LED_3")
      (description "Typical INFRARED GaAs LED")
      (fields (field (name "PUBLISHER") "Altium Limited"))
      (libsource (lib "Miscellaneous Devices") (part "LED0"))
    )
    (comp (ref "LED21")
      (value "LED0")
      (footprint "Device:LED_3")
      (description "Typical INFRARED GaAs LED")
      (fields (field (name "PUBLISHER") "Altium Limited"))
      (libsource (lib "Miscellaneous Devices") (part "LED0"))
    )
    (comp (ref "LED22")
      (value "LED0")
      (footprint "Device:LED_3")
      (description "Typical INFRARED GaAs LED")
      (fields (field (name "PUBLISHER") "Altium Limited"))
      (libsource (lib "Miscellaneous Devices") (part "LED0"))
    )
    (comp (ref "LED23")
      (value "LED0")
      (footprint "Device:LED_3")
      (description "Typical INFRARED GaAs LED")
      (fields (field (name "PUBLISHER") "Altium Limited"))
      (libsource (lib "Miscellaneous Devices") (part "LED0"))
    )
    (comp (ref "LED24")
      (value "LED0")
      (footprint "Device:LED_3")
      (description "Typical INFRARED GaAs LED")
      (fields (field (name "PUBLISHER") "Altium Limited"))
      (libsource (lib "Miscellaneous Devices") (part "LED0"))
    )
    (comp (ref "LED25")
      (value "LED0")
      (footprint "Device:LED_3")
      (description "Typical INFRARED GaAs LED")
      (fields (field (name "PUBLISHER") "Altium Limited"))
      (libsource (lib "Miscellaneous Devices") (part "LED0"))
    )
    (comp (ref "LED26")
      (value "LED0")
      (footprint "Device:LED_3")
      (description "Typical INFRARED GaAs LED")
      (fields (field (name "PUBLISHER") "Altium Limited"))
      (libsource (lib "Miscellaneous Devices") (part "LED0"))
    )
    (comp (ref "LED27")
      (value "LED0")
      (footprint "Device:LED_3")
      (description "Typical INFRARED GaAs LED")
      (fields (field (name "PUBLISHER") "Altium Limited"))
      (libsource (lib "Miscellaneous Devices") (part "LED0"))
    )
    (comp (ref "LED28")
      (value "LED0")
      (footprint "Device:LED_3")
      (description "Typical INFRARED GaAs LED")
      (fields (field (name "PUBLISHER") "Altium Limited"))
      (libsource (lib "Miscellaneous Devices") (part "LED0"))
    )
    (comp (ref "LED29")
      (value "LED0")
      (footprint "Device:LED_3")
      (description "Typical INFRARED GaAs LED")
      (fields (field (name "PUBLISHER") "Altium Limited"))
      (libsource (lib "Miscellaneous Devices") (part "LED0"))
    )
    (comp (ref "LED30")
      (value "LED0")
      (footprint "Device:LED_3")
      (description "Typical INFRARED GaAs LED")
      (fields (field (name "PUBLISHER") "Altium Limited"))
      (libsource (lib "Miscellaneous Devices") (part "LED0"))
    )
    (comp (ref "LED31")
      (value "LED0")
      (footprint "Device:LED_3")
      (description "Typical INFRARED GaAs LED")
      (fields (field (name "PUBLISHER") "Altium Limited"))
      (libsource (lib "Miscellaneous Devices") (part "LED0"))
    )
    (comp (ref "LED32")
      (value "LED0")
      (footprint "Device:LED_3")
      (description "Typical INFRARED GaAs LED")
      (fields (field (name "PUBLISHER") "Altium Limited"))
      (libsource (lib "Miscellaneous Devices") (part "LED0"))
    )
    (comp (ref "LED33")
      (value "LED0")
      (footprint "Device:LED_3")
      (description "Typical INFRARED GaAs LED")
      (fields (field (name "PUBLISHER") "Altium Limited"))
      (libsource (lib "Miscellaneous Devices") (part "LED0"))
    )
    (comp (ref "LED34")
      (value "LED0")
      (footprint "Device:LED_3")
      (description "Typical INFRARED GaAs LED")
      (fields (field (name "PUBLISHER") "Altium Limited"))
      (libsource (lib "Miscellaneous Devices") (part "LED0"))
    )
    (comp (ref "LED35")
      (value "LED0")
      (footprint "Device:LED_3")
      (description "Typical INFRARED GaAs LED")
      (fields (field (name "PUBLISHER") "Altium Limited"))
      (libsource (lib "Miscellaneous Devices") (part "LED0"))
    )
    (comp (ref "LED36")
      (value "LED0")
      (footprint "Device:LED_3")
      (description "Typical INFRARED GaAs LED")
      (fields (field (name "PUBLISHER") "Altium Limited"))
      (libsource (lib "Miscellaneous Devices") (part "LED0"))
    )
    (comp (ref "LED37")
      (value "LED0")
      (footprint "Device:LED_3")
      (description "Typical INFRARED GaAs LED")
      (fields (field (name "PUBLISHER") "Altium Limited"))
      (libsource (lib "Miscellaneous Devices") (part "LED0"))
    )
    (comp (ref "LED38")
      (value "LED0")
      (footprint "Device:LED_3")
      (description "Typical INFRARED GaAs LED")
      (fields (field (name "PUBLISHER") "Altium Limited"))
      (libsource (lib "Miscellaneous Devices") (part "LED0"))
    )
    (comp (ref "LED39")
      (value "LED0")
      (footprint "Device:LED_3")
      (description "Typical INFRARED GaAs LED")
      (fields (field (name "PUBLISHER") "Altium Limited"))
      (libsource (lib "Miscellaneous Devices") (part "LED0"))
    )
    (comp (ref "LED40")
      (value "LED0")
      (footprint "Device:LED_3")
      (description "Typical INFRARED GaAs LED")
      (fields (field (name "PUBLISHER") "Altium Limited"))
      (libsource (lib "Miscellaneous Devices") (part "LED0"))
    )
    (comp (ref "M1")
      (value "Header 10X2")
      (footprint "HDR2X10")
      (description "Header, 10-Pin, Dual row")
      (fields (field (name "PUBLISHER") "Altium Limited"))
      (libsource (lib "Miscellaneous Connectors") (part "Header 10X2"))
    )
    (comp (ref "M2")
      (value "Header 10X2")
      (footprint "HDR2X10")
      (description "Header, 10-Pin, Dual row")
      (fields (field (name "PUBLISHER") "Altium Limited"))
      (libsource (lib "Miscellaneous Connectors") (part "Header 10X2"))
    )
    (comp (ref "Power")
      (value "Header 2")
      (footprint "Device:Header_nguon_20A")
      (description "Header, 2-Pin")
      (fields (field (name "PUBLISHER") "Altium Limited"))
      (libsource (lib "Miscellaneous Connectors") (part "Header 2"))
    )
    (comp (ref "Q19")
      (value "2N3904")
      (footprint "Device:D468/A1013")
      (description "NPN General Purpose Amplifier")
      (fields (field (name "PUBLISHER") "Altium Limited"))
      (libsource (lib "Miscellaneous Devices") (part "2N3904"))
    )
    (comp (ref "R1")
      (value "10k")
      (footprint "Device:R_Nor")
      (description "Resistor")
      (fields (field (name "Comment") "Res3") (field (name "PUBLISHER") "Altium Limited"))
      (libsource (lib "Miscellaneous Devices") (part "Res3"))
    )
    (comp (ref "R2")
      (value "10k")
      (footprint "Device:R_Nor")
      (description "Resistor")
      (fields (field (name "Comment") "Res3") (field (name "PUBLISHER") "Altium Limited"))
      (libsource (lib "Miscellaneous Devices") (part "Res3"))
    )
    (comp (ref "R3")
      (value "10k")
      (footprint "Device:R_Nor")
      (description "Resistor")
      (fields (field (name "Comment") "Res3") (field (name "PUBLISHER") "Altium Limited"))
      (libsource (lib "Miscellaneous Devices") (part "Res3"))
    )
    (comp (ref "R4")
      (value "10k")
      (footprint "Device:R_Nor")
      (description "Resistor")
      (fields (field (name "Comment") "Res3") (field (name "PUBLISHER") "Altium Limited"))
      (libsource (lib "Miscellaneous Devices") (part "Res3"))
    )
    (comp (ref "R5")
      (value "10k")
      (footprint "Device:R_Nor")
      (description "Resistor")
      (fields (field (name "Comment") "Res3") (field (name "PUBLISHER") "Altium Limited"))
      (libsource (lib "Miscellaneous Devices") (part "Res3"))
    )
    (comp (ref "R6")
      (value "10k")
      (footprint "Device:R_Nor")
      (description "Resistor")
      (fields (field (name "Comment") "Res3") (field (name "PUBLISHER") "Altium Limited"))
      (libsource (lib "Miscellaneous Devices") (part "Res3"))
    )
    (comp (ref "R7")
      (value "10k")
      (footprint "Device:R_Nor")
      (description "Resistor")
      (fields (field (name "Comment") "Res3") (field (name "PUBLISHER") "Altium Limited"))
      (libsource (lib "Miscellaneous Devices") (part "Res3"))
    )
    (comp (ref "R8")
      (value "10k")
      (footprint "Device:R_Nor")
      (description "Resistor")
      (fields (field (name "Comment") "Res3") (field (name "PUBLISHER") "Altium Limited"))
      (libsource (lib "Miscellaneous Devices") (part "Res3"))
    )
    (comp (ref "R9")
      (value "10k")
      (footprint "Device:R_Nor")
      (description "Resistor")
      (fields (field (name "Comment") "Res3") (field (name "PUBLISHER") "Altium Limited"))
      (libsource (lib "Miscellaneous Devices") (part "Res3"))
    )
    (comp (ref "R10")
      (value "10k")
      (footprint "Device:R_Nor")
      (description "Resistor")
      (fields (field (name "Comment") "Res3") (field (name "PUBLISHER") "Altium Limited"))
      (libsource (lib "Miscellaneous Devices") (part "Res3"))
    )
    (comp (ref "R11")
      (value "10k")
      (footprint "Device:R_Nor")
      (description "Resistor")
      (fields (field (name "Comment") "Res3") (field (name "PUBLISHER") "Altium Limited"))
      (libsource (lib "Miscellaneous Devices") (part "Res3"))
    )
    (comp (ref "R12")
      (value "10k")
      (footprint "Device:R_Nor")
      (description "Resistor")
      (fields (field (name "Comment") "Res3") (field (name "PUBLISHER") "Altium Limited"))
      (libsource (lib "Miscellaneous Devices") (part "Res3"))
    )
    (comp (ref "R13")
      (value "10k")
      (footprint "Device:R_Nor")
      (description "Resistor")
      (fields (field (name "Comment") "Res3") (field (name "PUBLISHER") "Altium Limited"))
      (libsource (lib "Miscellaneous Devices") (part "Res3"))
    )
    (comp (ref "R14")
      (value "10k")
      (footprint "Device:R_Nor")
      (description "Resistor")
      (fields (field (name "Comment") "Res3") (field (name "PUBLISHER") "Altium Limited"))
      (libsource (lib "Miscellaneous Devices") (part "Res3"))
    )
    (comp (ref "R15")
      (value "10k")
      (footprint "Device:R_Nor")
      (description "Resistor")
      (fields (field (name "Comment") "Res3") (field (name "PUBLISHER") "Altium Limited"))
      (libsource (lib "Miscellaneous Devices") (part "Res3"))
    )
    (comp (ref "R16")
      (value "10k")
      (footprint "Device:R_Nor")
      (description "Resistor")
      (fields (field (name "Comment") "Res3") (field (name "PUBLISHER") "Altium Limited"))
      (libsource (lib "Miscellaneous Devices") (part "Res3"))
    )
    (comp (ref "R17")
      (value "10k")
      (footprint "Device:R_Nor")
      (description "Resistor")
      (fields (field (name "Comment") "Res3") (field (name "PUBLISHER") "Altium Limited"))
      (libsource (lib "Miscellaneous Devices") (part "Res3"))
    )
    (comp (ref "R18")
      (value "10k")
      (footprint "Device:R_Nor")
      (description "Resistor")
      (fields (field (name "Comment") "Res3") (field (name "PUBLISHER") "Altium Limited"))
      (libsource (lib "Miscellaneous Devices") (part "Res3"))
    )
    (comp (ref "R19")
      (value "10k")
      (footprint "Device:R_Nor")
      (description "Resistor")
      (fields (field (name "Comment") "Res3") (field (name "PUBLISHER") "Altium Limited"))
      (libsource (lib "Miscellaneous Devices") (part "Res3"))
    )
    (comp (ref "R20")
      (value "10k")
      (footprint "Device:R_Nor")
      (description "Resistor")
      (fields (field (name "Comment") "Res3") (field (name "PUBLISHER") "Altium Limited"))
      (libsource (lib "Miscellaneous Devices") (part "Res3"))
    )
    (comp (ref "R21")
      (value "10k")
      (footprint "Device:R_Nor")
      (description "Resistor")
      (fields (field (name "Comment") "Res3") (field (name "PUBLISHER") "Altium Limited"))
      (libsource (lib "Miscellaneous Devices") (part "Res3"))
    )
    (comp (ref "R22")
      (value "10k")
      (footprint "Device:R_Nor")
      (description "Resistor")
      (fields (field (name "Comment") "Res3") (field (name "PUBLISHER") "Altium Limited"))
      (libsource (lib "Miscellaneous Devices") (part "Res3"))
    )
    (comp (ref "R23")
      (value "10k")
      (footprint "Device:R_Nor")
      (description "Resistor")
      (fields (field (name "Comment") "Res3") (field (name "PUBLISHER") "Altium Limited"))
      (libsource (lib "Miscellaneous Devices") (part "Res3"))
    )
    (comp (ref "R24")
      (value "10k")
      (footprint "Device:R_Nor")
      (description "Resistor")
      (fields (field (name "Comment") "Res3") (field (name "PUBLISHER") "Altium Limited"))
      (libsource (lib "Miscellaneous Devices") (part "Res3"))
    )
    (comp (ref "R25")
      (value "10k")
      (footprint "Device:R_Nor")
      (description "Resistor")
      (fields (field (name "Comment") "Res3") (field (name "PUBLISHER") "Altium Limited"))
      (libsource (lib "Miscellaneous Devices") (part "Res3"))
    )
    (comp (ref "R26")
      (value "10k")
      (footprint "Device:R_Nor")
      (description "Resistor")
      (fields (field (name "Comment") "Res3") (field (name "PUBLISHER") "Altium Limited"))
      (libsource (lib "Miscellaneous Devices") (part "Res3"))
    )
    (comp (ref "R27")
      (value "10k")
      (footprint "Device:R_Nor")
      (description "Resistor")
      (fields (field (name "Comment") "Res3") (field (name "PUBLISHER") "Altium Limited"))
      (libsource (lib "Miscellaneous Devices") (part "Res3"))
    )
    (comp (ref "R28")
      (value "10k")
      (footprint "Device:R_Nor")
      (description "Resistor")
      (fields (field (name "Comment") "Res3") (field (name "PUBLISHER") "Altium Limited"))
      (libsource (lib "Miscellaneous Devices") (part "Res3"))
    )
    (comp (ref "R29")
      (value "10k")
      (footprint "Device:R_Nor")
      (description "Resistor")
      (fields (field (name "Comment") "Res3") (field (name "PUBLISHER") "Altium Limited"))
      (libsource (lib "Miscellaneous Devices") (part "Res3"))
    )
    (comp (ref "R30")
      (value "10k")
      (footprint "Device:R_Nor")
      (description "Resistor")
      (fields (field (name "Comment") "Res3") (field (name "PUBLISHER") "Altium Limited"))
      (libsource (lib "Miscellaneous Devices") (part "Res3"))
    )
    (comp (ref "R31")
      (value "10k")
      (footprint "Device:R_Nor")
      (description "Resistor")
      (fields (field (name "Comment") "Res3") (field (name "PUBLISHER") "Altium Limited"))
      (libsource (lib "Miscellaneous Devices") (part "Res3"))
    )
    (comp (ref "R32")
      (value "10k")
      (footprint "Device:R_Nor")
      (description "Resistor")
      (fields (field (name "Comment") "Res3") (field (name "PUBLISHER") "Altium Limited"))
      (libsource (lib "Miscellaneous Devices") (part "Res3"))
    )
    (comp (ref "R33")
      (value "10k")
      (footprint "Device:R_Nor")
      (description "Resistor")
      (fields (field (name "Comment") "Res3") (field (name "PUBLISHER") "Altium Limited"))
      (libsource (lib "Miscellaneous Devices") (part "Res3"))
    )
    (comp (ref "R34")
      (value "10k")
      (footprint "Device:R_Nor")
      (description "Resistor")
      (fields (field (name "Comment") "Res3") (field (name "PUBLISHER") "Altium Limited"))
      (libsource (lib "Miscellaneous Devices") (part "Res3"))
    )
    (comp (ref "R35")
      (value "10k")
      (footprint "Device:R_Nor")
      (description "Resistor")
      (fields (field (name "Comment") "Res3") (field (name "PUBLISHER") "Altium Limited"))
      (libsource (lib "Miscellaneous Devices") (part "Res3"))
    )
    (comp (ref "R36")
      (value "10k")
      (footprint "Device:R_Nor")
      (description "Resistor")
      (fields (field (name "Comment") "Res3") (field (name "PUBLISHER") "Altium Limited"))
      (libsource (lib "Miscellaneous Devices") (part "Res3"))
    )
    (comp (ref "R37")
      (value "10k")
      (footprint "Device:R_Nor")
      (description "Resistor")
      (fields (field (name "Comment") "Res3") (field (name "PUBLISHER") "Altium Limited"))
      (libsource (lib "Miscellaneous Devices") (part "Res3"))
    )
    (comp (ref "R38")
      (value "10k")
      (footprint "Device:R_Nor")
      (description "Resistor")
      (fields (field (name "Comment") "Res3") (field (name "PUBLISHER") "Altium Limited"))
      (libsource (lib "Miscellaneous Devices") (part "Res3"))
    )
    (comp (ref "R39")
      (value "10k")
      (footprint "Device:R_Nor")
      (description "Resistor")
      (fields (field (name "Comment") "Res3") (field (name "PUBLISHER") "Altium Limited"))
      (libsource (lib "Miscellaneous Devices") (part "Res3"))
    )
    (comp (ref "R40")
      (value "10k")
      (footprint "Device:R_Nor")
      (description "Resistor")
      (fields (field (name "Comment") "Res3") (field (name "PUBLISHER") "Altium Limited"))
      (libsource (lib "Miscellaneous Devices") (part "Res3"))
    )
    (comp (ref "RL1")
      (value "Header 2")
      (footprint "Device:Header_nguon_20A")
      (description "Header, 2-Pin")
      (fields (field (name "PUBLISHER") "Altium Limited"))
      (libsource (lib "Miscellaneous Connectors") (part "Header 2"))
    )
    (comp (ref "RL2")
      (value "Header 2")
      (footprint "Device:Header_nguon_20A")
      (description "Header, 2-Pin")
      (fields (field (name "PUBLISHER") "Altium Limited"))
      (libsource (lib "Miscellaneous Connectors") (part "Header 2"))
    )
    (comp (ref "RL3")
      (value "Header 2")
      (footprint "Device:Header_nguon_20A")
      (description "Header, 2-Pin")
      (fields (field (name "PUBLISHER") "Altium Limited"))
      (libsource (lib "Miscellaneous Connectors") (part "Header 2"))
    )
    (comp (ref "RL4")
      (value "Header 2")
      (footprint "Device:Header_nguon_20A")
      (description "Header, 2-Pin")
      (fields (field (name "PUBLISHER") "Altium Limited"))
      (libsource (lib "Miscellaneous Connectors") (part "Header 2"))
    )
    (comp (ref "RL5")
      (value "Header 2")
      (footprint "Device:Header_nguon_20A")
      (description "Header, 2-Pin")
      (fields (field (name "PUBLISHER") "Altium Limited"))
      (libsource (lib "Miscellaneous Connectors") (part "Header 2"))
    )
    (comp (ref "RL6")
      (value "Header 2")
      (footprint "Device:Header_nguon_20A")
      (description "Header, 2-Pin")
      (fields (field (name "PUBLISHER") "Altium Limited"))
      (libsource (lib "Miscellaneous Connectors") (part "Header 2"))
    )
    (comp (ref "RL7")
      (value "Header 2")
      (footprint "Device:Header_nguon_20A")
      (description "Header, 2-Pin")
      (fields (field (name "PUBLISHER") "Altium Limited"))
      (libsource (lib "Miscellaneous Connectors") (part "Header 2"))
    )
    (comp (ref "RL8")
      (value "Header 2")
      (footprint "Device:Header_nguon_20A")
      (description "Header, 2-Pin")
      (fields (field (name "PUBLISHER") "Altium Limited"))
      (libsource (lib "Miscellaneous Connectors") (part "Header 2"))
    )
    (comp (ref "RL9")
      (value "Header 2")
      (footprint "Device:Header_nguon_20A")
      (description "Header, 2-Pin")
      (fields (field (name "PUBLISHER") "Altium Limited"))
      (libsource (lib "Miscellaneous Connectors") (part "Header 2"))
    )
    (comp (ref "RL10")
      (value "Header 2")
      (footprint "Device:Header_nguon_20A")
      (description "Header, 2-Pin")
      (fields (field (name "PUBLISHER") "Altium Limited"))
      (libsource (lib "Miscellaneous Connectors") (part "Header 2"))
    )
    (comp (ref "RL11")
      (value "Header 2")
      (footprint "Device:Header_nguon_20A")
      (description "Header, 2-Pin")
      (fields (field (name "PUBLISHER") "Altium Limited"))
      (libsource (lib "Miscellaneous Connectors") (part "Header 2"))
    )
    (comp (ref "RL12")
      (value "Header 2")
      (footprint "Device:Header_nguon_20A")
      (description "Header, 2-Pin")
      (fields (field (name "PUBLISHER") "Altium Limited"))
      (libsource (lib "Miscellaneous Connectors") (part "Header 2"))
    )
    (comp (ref "RL13")
      (value "Header 2")
      (footprint "Device:Header_nguon_20A")
      (description "Header, 2-Pin")
      (fields (field (name "PUBLISHER") "Altium Limited"))
      (libsource (lib "Miscellaneous Connectors") (part "Header 2"))
    )
    (comp (ref "RL14")
      (value "Header 2")
      (footprint "Device:Header_nguon_20A")
      (description "Header, 2-Pin")
      (fields (field (name "PUBLISHER") "Altium Limited"))
      (libsource (lib "Miscellaneous Connectors") (part "Header 2"))
    )
    (comp (ref "RL15")
      (value "Header 2")
      (footprint "Device:Header_nguon_20A")
      (description "Header, 2-Pin")
      (fields (field (name "PUBLISHER") "Altium Limited"))
      (libsource (lib "Miscellaneous Connectors") (part "Header 2"))
    )
    (comp (ref "RL16")
      (value "Header 2")
      (footprint "Device:Header_nguon_20A")
      (description "Header, 2-Pin")
      (fields (field (name "PUBLISHER") "Altium Limited"))
      (libsource (lib "Miscellaneous Connectors") (part "Header 2"))
    )
    (comp (ref "RL17")
      (value "Header 2")
      (footprint "Device:Header_nguon_20A")
      (description "Header, 2-Pin")
      (fields (field (name "PUBLISHER") "Altium Limited"))
      (libsource (lib "Miscellaneous Connectors") (part "Header 2"))
    )
    (comp (ref "RL18")
      (value "Header 2")
      (footprint "Device:Header_nguon_20A")
      (description "Header, 2-Pin")
      (fields (field (name "PUBLISHER") "Altium Limited"))
      (libsource (lib "Miscellaneous Connectors") (part "Header 2"))
    )
    (comp (ref "RL19")
      (value "Header 2")
      (footprint "Device:Header_nguon_20A")
      (description "Header, 2-Pin")
      (fields (field (name "PUBLISHER") "Altium Limited"))
      (libsource (lib "Miscellaneous Connectors") (part "Header 2"))
    )
    (comp (ref "RL20")
      (value "Header 2")
      (footprint "Device:Header_nguon_20A")
      (description "Header, 2-Pin")
      (fields (field (name "PUBLISHER") "Altium Limited"))
      (libsource (lib "Miscellaneous Connectors") (part "Header 2"))
    )
    (comp (ref "RL21")
      (value "Header 2")
      (footprint "Device:Header_nguon_20A")
      (description "Header, 2-Pin")
      (fields (field (name "PUBLISHER") "Altium Limited"))
      (libsource (lib "Miscellaneous Connectors") (part "Header 2"))
    )
    (comp (ref "RL22")
      (value "Header 2")
      (footprint "Device:Header_nguon_20A")
      (description "Header, 2-Pin")
      (fields (field (name "PUBLISHER") "Altium Limited"))
      (libsource (lib "Miscellaneous Connectors") (part "Header 2"))
    )
    (comp (ref "RL23")
      (value "Header 2")
      (footprint "Device:Header_nguon_20A")
      (description "Header, 2-Pin")
      (fields (field (name "PUBLISHER") "Altium Limited"))
      (libsource (lib "Miscellaneous Connectors") (part "Header 2"))
    )
    (comp (ref "RL24")
      (value "Header 2")
      (footprint "Device:Header_nguon_20A")
      (description "Header, 2-Pin")
      (fields (field (name "PUBLISHER") "Altium Limited"))
      (libsource (lib "Miscellaneous Connectors") (part "Header 2"))
    )
    (comp (ref "RL25")
      (value "Header 2")
      (footprint "Device:Header_nguon_20A")
      (description "Header, 2-Pin")
      (fields (field (name "PUBLISHER") "Altium Limited"))
      (libsource (lib "Miscellaneous Connectors") (part "Header 2"))
    )
    (comp (ref "RL26")
      (value "Header 2")
      (footprint "Device:Header_nguon_20A")
      (description "Header, 2-Pin")
      (fields (field (name "PUBLISHER") "Altium Limited"))
      (libsource (lib "Miscellaneous Connectors") (part "Header 2"))
    )
    (comp (ref "RL27")
      (value "Header 2")
      (footprint "Device:Header_nguon_20A")
      (description "Header, 2-Pin")
      (fields (field (name "PUBLISHER") "Altium Limited"))
      (libsource (lib "Miscellaneous Connectors") (part "Header 2"))
    )
    (comp (ref "RL28")
      (value "Header 2")
      (footprint "Device:Header_nguon_20A")
      (description "Header, 2-Pin")
      (fields (field (name "PUBLISHER") "Altium Limited"))
      (libsource (lib "Miscellaneous Connectors") (part "Header 2"))
    )
    (comp (ref "RL29")
      (value "Header 2")
      (footprint "Device:Header_nguon_20A")
      (description "Header, 2-Pin")
      (fields (field (name "PUBLISHER") "Altium Limited"))
      (libsource (lib "Miscellaneous Connectors") (part "Header 2"))
    )
    (comp (ref "RL30")
      (value "Header 2")
      (footprint "Device:Header_nguon_20A")
      (description "Header, 2-Pin")
      (fields (field (name "PUBLISHER") "Altium Limited"))
      (libsource (lib "Miscellaneous Connectors") (part "Header 2"))
    )
    (comp (ref "RL31")
      (value "Header 2")
      (footprint "Device:Header_nguon_20A")
      (description "Header, 2-Pin")
      (fields (field (name "PUBLISHER") "Altium Limited"))
      (libsource (lib "Miscellaneous Connectors") (part "Header 2"))
    )
    (comp (ref "RL32")
      (value "Header 2")
      (footprint "Device:Header_nguon_20A")
      (description "Header, 2-Pin")
      (fields (field (name "PUBLISHER") "Altium Limited"))
      (libsource (lib "Miscellaneous Connectors") (part "Header 2"))
    )
    (comp (ref "RL33")
      (value "Header 2")
      (footprint "Device:Header_nguon_20A")
      (description "Header, 2-Pin")
      (fields (field (name "PUBLISHER") "Altium Limited"))
      (libsource (lib "Miscellaneous Connectors") (part "Header 2"))
    )
    (comp (ref "RL34")
      (value "Header 2")
      (footprint "Device:Header_nguon_20A")
      (description "Header, 2-Pin")
      (fields (field (name "PUBLISHER") "Altium Limited"))
      (libsource (lib "Miscellaneous Connectors") (part "Header 2"))
    )
    (comp (ref "RL35")
      (value "Header 2")
      (footprint "Device:Header_nguon_20A")
      (description "Header, 2-Pin")
      (fields (field (name "PUBLISHER") "Altium Limited"))
      (libsource (lib "Miscellaneous Connectors") (part "Header 2"))
    )
    (comp (ref "RL36")
      (value "Header 2")
      (footprint "Device:Header_nguon_20A")
      (description "Header, 2-Pin")
      (fields (field (name "PUBLISHER") "Altium Limited"))
      (libsource (lib "Miscellaneous Connectors") (part "Header 2"))
    )
    (comp (ref "RL37")
      (value "Header 2")
      (footprint "Device:Header_nguon_20A")
      (description "Header, 2-Pin")
      (fields (field (name "PUBLISHER") "Altium Limited"))
      (libsource (lib "Miscellaneous Connectors") (part "Header 2"))
    )
    (comp (ref "RL38")
      (value "Header 2")
      (footprint "Device:Header_nguon_20A")
      (description "Header, 2-Pin")
      (fields (field (name "PUBLISHER") "Altium Limited"))
      (libsource (lib "Miscellaneous Connectors") (part "Header 2"))
    )
    (comp (ref "RL39")
      (value "Header 2")
      (footprint "Device:Header_nguon_20A")
      (description "Header, 2-Pin")
      (fields (field (name "PUBLISHER") "Altium Limited"))
      (libsource (lib "Miscellaneous Connectors") (part "Header 2"))
    )
    (comp (ref "RL40")
      (value "Header 2")
      (footprint "Device:Header_nguon_20A")
      (description "Header, 2-Pin")
      (fields (field (name "PUBLISHER") "Altium Limited"))
      (libsource (lib "Miscellaneous Connectors") (part "Header 2"))
    )
    (comp (ref "Rp2")
      (value "1K")
      (footprint "Device:R_Nor")
      (description "Resistor")
      (fields (field (name "Comment") "Res3") (field (name "PUBLISHER") "Altium Limited"))
      (libsource (lib "Miscellaneous Devices") (part "Res3"))
    )
  )
  (nets
    (net (code "1") (name "+12V") (class "Default")
      (node (ref "C1") (pin "1") (pinfunction "1_1") (pintype "passive"))
      (node (ref "D1") (pin "2") (pinfunction "K_2") (pintype "passive"))
      (node (ref "D10") (pin "2") (pinfunction "K_2") (pintype "passive"))
      (node (ref "D11") (pin "2") (pinfunction "K_2") (pintype "passive"))
      (node (ref "D12") (pin "2") (pinfunction "K_2") (pintype "passive"))
      (node (ref "D13") (pin "2") (pinfunction "K_2") (pintype "passive"))
      (node (ref "D14") (pin "2") (pinfunction "K_2") (pintype "passive"))
      (node (ref "D15") (pin "2") (pinfunction "K_2") (pintype "passive"))
      (node (ref "D16") (pin "2") (pinfunction "K_2") (pintype "passive"))
      (node (ref "D17") (pin "2") (pinfunction "K_2") (pintype "passive"))
      (node (ref "D18") (pin "2") (pinfunction "K_2") (pintype "passive"))
      (node (ref "D19") (pin "2") (pinfunction "K_2") (pintype "passive"))
      (node (ref "D2") (pin "2") (pinfunction "K_2") (pintype "passive"))
      (node (ref "D20") (pin "2") (pinfunction "K_2") (pintype "passive"))
      (node (ref "D21") (pin "2") (pinfunction "K_2") (pintype "passive"))
      (node (ref "D22") (pin "2") (pinfunction "K_2") (pintype "passive"))
      (node (ref "D23") (pin "2") (pinfunction "K_2") (pintype "passive"))
      (node (ref "D24") (pin "2") (pinfunction "K_2") (pintype "passive"))
      (node (ref "D25") (pin "2") (pinfunction "K_2") (pintype "passive"))
      (node (ref "D26") (pin "2") (pinfunction "K_2") (pintype "passive"))
      (node (ref "D27") (pin "2") (pinfunction "K_2") (pintype "passive"))
      (node (ref "D28") (pin "2") (pinfunction "K_2") (pintype "passive"))
      (node (ref "D29") (pin "2") (pinfunction "K_2") (pintype "passive"))
      (node (ref "D3") (pin "2") (pinfunction "K_2") (pintype "passive"))
      (node (ref "D30") (pin "2") (pinfunction "K_2") (pintype "passive"))
      (node (ref "D31") (pin "2") (pinfunction "K_2") (pintype "passive"))
      (node (ref "D32") (pin "2") (pinfunction "K_2") (pintype "passive"))
      (node (ref "D33") (pin "2") (pinfunction "K_2") (pintype "passive"))
      (node (ref "D34") (pin "2") (pinfunction "K_2") (pintype "passive"))
      (node (ref "D35") (pin "2") (pinfunction "K_2") (pintype "passive"))
      (node (ref "D36") (pin "2") (pinfunction "K_2") (pintype "passive"))
      (node (ref "D37") (pin "2") (pinfunction "K_2") (pintype "passive"))
      (node (ref "D38") (pin "2") (pinfunction "K_2") (pintype "passive"))
      (node (ref "D39") (pin "2") (pinfunction "K_2") (pintype "passive"))
      (node (ref "D4") (pin "2") (pinfunction "K_2") (pintype "passive"))
      (node (ref "D40") (pin "2") (pinfunction "K_2") (pintype "passive"))
      (node (ref "D5") (pin "2") (pinfunction "K_2") (pintype "passive"))
      (node (ref "D6") (pin "2") (pinfunction "K_2") (pintype "passive"))
      (node (ref "D7") (pin "2") (pinfunction "K_2") (pintype "passive"))
      (node (ref "D8") (pin "2") (pinfunction "K_2") (pintype "passive"))
      (node (ref "D9") (pin "2") (pinfunction "K_2") (pintype "passive"))
      (node (ref "K1") (pin "3") (pinfunction "3_3") (pintype "passive"))
      (node (ref "K10") (pin "3") (pinfunction "3_3") (pintype "passive"))
      (node (ref "K11") (pin "3") (pinfunction "3_3") (pintype "passive"))
      (node (ref "K12") (pin "3") (pinfunction "3_3") (pintype "passive"))
      (node (ref "K13") (pin "3") (pinfunction "3_3") (pintype "passive"))
      (node (ref "K14") (pin "3") (pinfunction "3_3") (pintype "passive"))
      (node (ref "K15") (pin "3") (pinfunction "3_3") (pintype "passive"))
      (node (ref "K16") (pin "3") (pinfunction "3_3") (pintype "passive"))
      (node (ref "K17") (pin "3") (pinfunction "3_3") (pintype "passive"))
      (node (ref "K18") (pin "3") (pinfunction "3_3") (pintype "passive"))
      (node (ref "K19") (pin "3") (pinfunction "3_3") (pintype "passive"))
      (node (ref "K2") (pin "3") (pinfunction "3_3") (pintype "passive"))
      (node (ref "K20") (pin "3") (pinfunction "3_3") (pintype "passive"))
      (node (ref "K21") (pin "3") (pinfunction "3_3") (pintype "passive"))
      (node (ref "K22") (pin "3") (pinfunction "3_3") (pintype "passive"))
      (node (ref "K23") (pin "3") (pinfunction "3_3") (pintype "passive"))
      (node (ref "K24") (pin "3") (pinfunction "3_3") (pintype "passive"))
      (node (ref "K25") (pin "3") (pinfunction "3_3") (pintype "passive"))
      (node (ref "K26") (pin "3") (pinfunction "3_3") (pintype "passive"))
      (node (ref "K27") (pin "3") (pinfunction "3_3") (pintype "passive"))
      (node (ref "K28") (pin "3") (pinfunction "3_3") (pintype "passive"))
      (node (ref "K29") (pin "3") (pinfunction "3_3") (pintype "passive"))
      (node (ref "K3") (pin "3") (pinfunction "3_3") (pintype "passive"))
      (node (ref "K30") (pin "3") (pinfunction "3_3") (pintype "passive"))
      (node (ref "K31") (pin "3") (pinfunction "3_3") (pintype "passive"))
      (node (ref "K32") (pin "3") (pinfunction "3_3") (pintype "passive"))
      (node (ref "K33") (pin "3") (pinfunction "3_3") (pintype "passive"))
      (node (ref "K34") (pin "3") (pinfunction "3_3") (pintype "passive"))
      (node (ref "K35") (pin "3") (pinfunction "3_3") (pintype "passive"))
      (node (ref "K36") (pin "3") (pinfunction "3_3") (pintype "passive"))
      (node (ref "K37") (pin "3") (pinfunction "3_3") (pintype "passive"))
      (node (ref "K38") (pin "3") (pinfunction "3_3") (pintype "passive"))
      (node (ref "K39") (pin "3") (pinfunction "3_3") (pintype "passive"))
      (node (ref "K4") (pin "3") (pinfunction "3_3") (pintype "passive"))
      (node (ref "K40") (pin "3") (pinfunction "3_3") (pintype "passive"))
      (node (ref "K5") (pin "3") (pinfunction "3_3") (pintype "passive"))
      (node (ref "K6") (pin "3") (pinfunction "3_3") (pintype "passive"))
      (node (ref "K7") (pin "3") (pinfunction "3_3") (pintype "passive"))
      (node (ref "K8") (pin "3") (pinfunction "3_3") (pintype "passive"))
      (node (ref "K9") (pin "3") (pinfunction "3_3") (pintype "passive"))
      (node (ref "Power") (pin "1") (pinfunction "1_1") (pintype "passive"))
      (node (ref "R1") (pin "1") (pinfunction "1_1") (pintype "passive"))
      (node (ref "R10") (pin "1") (pinfunction "1_1") (pintype "passive"))
      (node (ref "R11") (pin "1") (pinfunction "1_1") (pintype "passive"))
      (node (ref "R12") (pin "1") (pinfunction "1_1") (pintype "passive"))
      (node (ref "R13") (pin "1") (pinfunction "1_1") (pintype "passive"))
      (node (ref "R14") (pin "1") (pinfunction "1_1") (pintype "passive"))
      (node (ref "R15") (pin "1") (pinfunction "1_1") (pintype "passive"))
      (node (ref "R16") (pin "1") (pinfunction "1_1") (pintype "passive"))
      (node (ref "R17") (pin "1") (pinfunction "1_1") (pintype "passive"))
      (node (ref "R18") (pin "1") (pinfunction "1_1") (pintype "passive"))
      (node (ref "R19") (pin "1") (pinfunction "1_1") (pintype "passive"))
      (node (ref "R2") (pin "1") (pinfunction "1_1") (pintype "passive"))
      (node (ref "R20") (pin "1") (pinfunction "1_1") (pintype "passive"))
      (node (ref "R21") (pin "1") (pinfunction "1_1") (pintype "passive"))
      (node (ref "R22") (pin "1") (pinfunction "1_1") (pintype "passive"))
      (node (ref "R23") (pin "1") (pinfunction "1_1") (pintype "passive"))
      (node (ref "R24") (pin "1") (pinfunction "1_1") (pintype "passive"))
      (node (ref "R25") (pin "1") (pinfunction "1_1") (pintype "passive"))
      (node (ref "R26") (pin "1") (pinfunction "1_1") (pintype "passive"))
      (node (ref "R27") (pin "1") (pinfunction "1_1") (pintype "passive"))
      (node (ref "R28") (pin "1") (pinfunction "1_1") (pintype "passive"))
      (node (ref "R29") (pin "1") (pinfunction "1_1") (pintype "passive"))
      (node (ref "R3") (pin "1") (pinfunction "1_1") (pintype "passive"))
      (node (ref "R30") (pin "1") (pinfunction "1_1") (pintype "passive"))
      (node (ref "R31") (pin "1") (pinfunction "1_1") (pintype "passive"))
      (node (ref "R32") (pin "1") (pinfunction "1_1") (pintype "passive"))
      (node (ref "R33") (pin "1") (pinfunction "1_1") (pintype "passive"))
      (node (ref "R34") (pin "1") (pinfunction "1_1") (pintype "passive"))
      (node (ref "R35") (pin "1") (pinfunction "1_1") (pintype "passive"))
      (node (ref "R36") (pin "1") (pinfunction "1_1") (pintype "passive"))
      (node (ref "R37") (pin "1") (pinfunction "1_1") (pintype "passive"))
      (node (ref "R38") (pin "1") (pinfunction "1_1") (pintype "passive"))
      (node (ref "R39") (pin "1") (pinfunction "1_1") (pintype "passive"))
      (node (ref "R4") (pin "1") (pinfunction "1_1") (pintype "passive"))
      (node (ref "R40") (pin "1") (pinfunction "1_1") (pintype "passive"))
      (node (ref "R5") (pin "1") (pinfunction "1_1") (pintype "passive"))
      (node (ref "R6") (pin "1") (pinfunction "1_1") (pintype "passive"))
      (node (ref "R7") (pin "1") (pinfunction "1_1") (pintype "passive"))
      (node (ref "R8") (pin "1") (pinfunction "1_1") (pintype "passive"))
      (node (ref "R9") (pin "1") (pinfunction "1_1") (pintype "passive"))
      (node (ref "Rp2") (pin "1") (pinfunction "1_1") (pintype "passive"))
    )
    (net (code "2") (name "/RL1") (class "Default")
      (node (ref "D1") (pin "1") (pinfunction "A_1") (pintype "passive"))
      (node (ref "K1") (pin "4") (pinfunction "4_4") (pintype "passive"))
      (node (ref "LED1") (pin "2") (pinfunction "K_2") (pintype "passive"))
      (node (ref "M1") (pin "16") (pinfunction "16_16") (pintype "passive"))
    )
    (net (code "3") (name "/RL2") (class "Default")
      (node (ref "D2") (pin "1") (pinfunction "A_1") (pintype "passive"))
      (node (ref "K2") (pin "4") (pinfunction "4_4") (pintype "passive"))
      (node (ref "LED2") (pin "2") (pinfunction "K_2") (pintype "passive"))
      (node (ref "M1") (pin "14") (pinfunction "14_14") (pintype "passive"))
    )
    (net (code "4") (name "/RL3") (class "Default")
      (node (ref "D3") (pin "1") (pinfunction "A_1") (pintype "passive"))
      (node (ref "K3") (pin "4") (pinfunction "4_4") (pintype "passive"))
      (node (ref "LED3") (pin "2") (pinfunction "K_2") (pintype "passive"))
      (node (ref "M1") (pin "12") (pinfunction "12_12") (pintype "passive"))
    )
    (net (code "5") (name "/RL4") (class "Default")
      (node (ref "D4") (pin "1") (pinfunction "A_1") (pintype "passive"))
      (node (ref "K4") (pin "4") (pinfunction "4_4") (pintype "passive"))
      (node (ref "LED4") (pin "2") (pinfunction "K_2") (pintype "passive"))
      (node (ref "M1") (pin "10") (pinfunction "10_10") (pintype "passive"))
    )
    (net (code "6") (name "/RL5") (class "Default")
      (node (ref "D5") (pin "1") (pinfunction "A_1") (pintype "passive"))
      (node (ref "K5") (pin "4") (pinfunction "4_4") (pintype "passive"))
      (node (ref "LED5") (pin "2") (pinfunction "K_2") (pintype "passive"))
      (node (ref "M1") (pin "8") (pinfunction "8_8") (pintype "passive"))
    )
    (net (code "7") (name "/RL6") (class "Default")
      (node (ref "D6") (pin "1") (pinfunction "A_1") (pintype "passive"))
      (node (ref "K6") (pin "4") (pinfunction "4_4") (pintype "passive"))
      (node (ref "LED6") (pin "2") (pinfunction "K_2") (pintype "passive"))
      (node (ref "M1") (pin "6") (pinfunction "6_6") (pintype "passive"))
    )
    (net (code "8") (name "/RL7") (class "Default")
      (node (ref "D7") (pin "1") (pinfunction "A_1") (pintype "passive"))
      (node (ref "K7") (pin "4") (pinfunction "4_4") (pintype "passive"))
      (node (ref "LED7") (pin "2") (pinfunction "K_2") (pintype "passive"))
      (node (ref "M1") (pin "4") (pinfunction "4_4") (pintype "passive"))
    )
    (net (code "9") (name "/RL8") (class "Default")
      (node (ref "D8") (pin "1") (pinfunction "A_1") (pintype "passive"))
      (node (ref "K8") (pin "4") (pinfunction "4_4") (pintype "passive"))
      (node (ref "LED8") (pin "2") (pinfunction "K_2") (pintype "passive"))
      (node (ref "M1") (pin "2") (pinfunction "2_2") (pintype "passive"))
    )
    (net (code "10") (name "/RL9") (class "Default")
      (node (ref "D9") (pin "1") (pinfunction "A_1") (pintype "passive"))
      (node (ref "K9") (pin "4") (pinfunction "4_4") (pintype "passive"))
      (node (ref "LED9") (pin "2") (pinfunction "K_2") (pintype "passive"))
      (node (ref "M2") (pin "12") (pinfunction "12_12") (pintype "passive"))
    )
    (net (code "11") (name "/RL10") (class "Default")
      (node (ref "D10") (pin "1") (pinfunction "A_1") (pintype "passive"))
      (node (ref "K10") (pin "4") (pinfunction "4_4") (pintype "passive"))
      (node (ref "LED10") (pin "2") (pinfunction "K_2") (pintype "passive"))
      (node (ref "M2") (pin "10") (pinfunction "10_10") (pintype "passive"))
    )
    (net (code "12") (name "/RL11") (class "Default")
      (node (ref "D11") (pin "1") (pinfunction "A_1") (pintype "passive"))
      (node (ref "K11") (pin "4") (pinfunction "4_4") (pintype "passive"))
      (node (ref "LED11") (pin "2") (pinfunction "K_2") (pintype "passive"))
      (node (ref "M2") (pin "8") (pinfunction "8_8") (pintype "passive"))
    )
    (net (code "13") (name "/RL12") (class "Default")
      (node (ref "D12") (pin "1") (pinfunction "A_1") (pintype "passive"))
      (node (ref "K12") (pin "4") (pinfunction "4_4") (pintype "passive"))
      (node (ref "LED12") (pin "2") (pinfunction "K_2") (pintype "passive"))
      (node (ref "M2") (pin "6") (pinfunction "6_6") (pintype "passive"))
    )
    (net (code "14") (name "/RL13") (class "Default")
      (node (ref "D13") (pin "1") (pinfunction "A_1") (pintype "passive"))
      (node (ref "K13") (pin "4") (pinfunction "4_4") (pintype "passive"))
      (node (ref "LED13") (pin "2") (pinfunction "K_2") (pintype "passive"))
      (node (ref "M2") (pin "4") (pinfunction "4_4") (pintype "passive"))
    )
    (net (code "15") (name "/RL14") (class "Default")
      (node (ref "D14") (pin "1") (pinfunction "A_1") (pintype "passive"))
      (node (ref "K14") (pin "4") (pinfunction "4_4") (pintype "passive"))
      (node (ref "LED14") (pin "2") (pinfunction "K_2") (pintype "passive"))
      (node (ref "M2") (pin "2") (pinfunction "2_2") (pintype "passive"))
    )
    (net (code "16") (name "/RL15") (class "Default")
      (node (ref "D15") (pin "1") (pinfunction "A_1") (pintype "passive"))
      (node (ref "K15") (pin "4") (pinfunction "4_4") (pintype "passive"))
      (node (ref "LED15") (pin "2") (pinfunction "K_2") (pintype "passive"))
      (node (ref "M1") (pin "20") (pinfunction "20_20") (pintype "passive"))
    )
    (net (code "17") (name "/RL16") (class "Default")
      (node (ref "D16") (pin "1") (pinfunction "A_1") (pintype "passive"))
      (node (ref "K16") (pin "4") (pinfunction "4_4") (pintype "passive"))
      (node (ref "LED16") (pin "2") (pinfunction "K_2") (pintype "passive"))
      (node (ref "M1") (pin "18") (pinfunction "18_18") (pintype "passive"))
    )
    (net (code "18") (name "/RL17") (class "Default")
      (node (ref "D17") (pin "1") (pinfunction "A_1") (pintype "passive"))
      (node (ref "K17") (pin "4") (pinfunction "4_4") (pintype "passive"))
      (node (ref "LED17") (pin "2") (pinfunction "K_2") (pintype "passive"))
      (node (ref "M2") (pin "13") (pinfunction "13_13") (pintype "passive"))
    )
    (net (code "19") (name "/RL18") (class "Default")
      (node (ref "D18") (pin "1") (pinfunction "A_1") (pintype "passive"))
      (node (ref "K18") (pin "4") (pinfunction "4_4") (pintype "passive"))
      (node (ref "LED18") (pin "2") (pinfunction "K_2") (pintype "passive"))
      (node (ref "M2") (pin "15") (pinfunction "15_15") (pintype "passive"))
    )
    (net (code "20") (name "/RL19") (class "Default")
      (node (ref "M2") (pin "17") (pinfunction "17_17") (pintype "passive"))
      (node (ref "Q19") (pin "3") (pinfunction "B_3") (pintype "passive"))
    )
    (net (code "21") (name "/RL20") (class "Default")
      (node (ref "D20") (pin "1") (pinfunction "A_1") (pintype "passive"))
      (node (ref "K20") (pin "4") (pinfunction "4_4") (pintype "passive"))
      (node (ref "LED20") (pin "2") (pinfunction "K_2") (pintype "passive"))
      (node (ref "M2") (pin "19") (pinfunction "19_19") (pintype "passive"))
    )
    (net (code "22") (name "/RL21") (class "Default")
      (node (ref "D21") (pin "1") (pinfunction "A_1") (pintype "passive"))
      (node (ref "K21") (pin "4") (pinfunction "4_4") (pintype "passive"))
      (node (ref "LED21") (pin "2") (pinfunction "K_2") (pintype "passive"))
      (node (ref "M2") (pin "20") (pinfunction "20_20") (pintype "passive"))
    )
    (net (code "23") (name "/RL22") (class "Default")
      (node (ref "D22") (pin "1") (pinfunction "A_1") (pintype "passive"))
      (node (ref "K22") (pin "4") (pinfunction "4_4") (pintype "passive"))
      (node (ref "LED22") (pin "2") (pinfunction "K_2") (pintype "passive"))
      (node (ref "M2") (pin "18") (pinfunction "18_18") (pintype "passive"))
    )
    (net (code "24") (name "/RL23") (class "Default")
      (node (ref "D23") (pin "1") (pinfunction "A_1") (pintype "passive"))
      (node (ref "K23") (pin "4") (pinfunction "4_4") (pintype "passive"))
      (node (ref "LED23") (pin "2") (pinfunction "K_2") (pintype "passive"))
      (node (ref "M2") (pin "16") (pinfunction "16_16") (pintype "passive"))
    )
    (net (code "25") (name "/RL24") (class "Default")
      (node (ref "D24") (pin "1") (pinfunction "A_1") (pintype "passive"))
      (node (ref "K24") (pin "4") (pinfunction "4_4") (pintype "passive"))
      (node (ref "LED24") (pin "2") (pinfunction "K_2") (pintype "passive"))
      (node (ref "M2") (pin "14") (pinfunction "14_14") (pintype "passive"))
    )
    (net (code "26") (name "/RL25") (class "Default")
      (node (ref "D25") (pin "1") (pinfunction "A_1") (pintype "passive"))
      (node (ref "K25") (pin "4") (pinfunction "4_4") (pintype "passive"))
      (node (ref "LED25") (pin "2") (pinfunction "K_2") (pintype "passive"))
      (node (ref "M1") (pin "17") (pinfunction "17_17") (pintype "passive"))
    )
    (net (code "27") (name "/RL26") (class "Default")
      (node (ref "D26") (pin "1") (pinfunction "A_1") (pintype "passive"))
      (node (ref "K26") (pin "4") (pinfunction "4_4") (pintype "passive"))
      (node (ref "LED26") (pin "2") (pinfunction "K_2") (pintype "passive"))
      (node (ref "M1") (pin "19") (pinfunction "19_19") (pintype "passive"))
    )
    (net (code "28") (name "/RL27") (class "Default")
      (node (ref "D27") (pin "1") (pinfunction "A_1") (pintype "passive"))
      (node (ref "K27") (pin "4") (pinfunction "4_4") (pintype "passive"))
      (node (ref "LED27") (pin "2") (pinfunction "K_2") (pintype "passive"))
      (node (ref "M2") (pin "1") (pinfunction "1_1") (pintype "passive"))
    )
    (net (code "29") (name "/RL28") (class "Default")
      (node (ref "D28") (pin "1") (pinfunction "A_1") (pintype "passive"))
      (node (ref "K28") (pin "4") (pinfunction "4_4") (pintype "passive"))
      (node (ref "LED28") (pin "2") (pinfunction "K_2") (pintype "passive"))
      (node (ref "M2") (pin "3") (pinfunction "3_3") (pintype "passive"))
    )
    (net (code "30") (name "/RL29") (class "Default")
      (node (ref "D29") (pin "1") (pinfunction "A_1") (pintype "passive"))
      (node (ref "K29") (pin "4") (pinfunction "4_4") (pintype "passive"))
      (node (ref "LED29") (pin "2") (pinfunction "K_2") (pintype "passive"))
      (node (ref "M2") (pin "5") (pinfunction "5_5") (pintype "passive"))
    )
    (net (code "31") (name "/RL30") (class "Default")
      (node (ref "D30") (pin "1") (pinfunction "A_1") (pintype "passive"))
      (node (ref "K30") (pin "4") (pinfunction "4_4") (pintype "passive"))
      (node (ref "LED30") (pin "2") (pinfunction "K_2") (pintype "passive"))
      (node (ref "M2") (pin "7") (pinfunction "7_7") (pintype "passive"))
    )
    (net (code "32") (name "/RL31") (class "Default")
      (node (ref "D31") (pin "1") (pinfunction "A_1") (pintype "passive"))
      (node (ref "K31") (pin "4") (pinfunction "4_4") (pintype "passive"))
      (node (ref "LED31") (pin "2") (pinfunction "K_2") (pintype "passive"))
      (node (ref "M2") (pin "9") (pinfunction "9_9") (pintype "passive"))
    )
    (net (code "33") (name "/RL32") (class "Default")
      (node (ref "D32") (pin "1") (pinfunction "A_1") (pintype "passive"))
      (node (ref "K32") (pin "4") (pinfunction "4_4") (pintype "passive"))
      (node (ref "LED32") (pin "2") (pinfunction "K_2") (pintype "passive"))
      (node (ref "M2") (pin "11") (pinfunction "11_11") (pintype "passive"))
    )
    (net (code "34") (name "/RL33") (class "Default")
      (node (ref "D33") (pin "1") (pinfunction "A_1") (pintype "passive"))
      (node (ref "K33") (pin "4") (pinfunction "4_4") (pintype "passive"))
      (node (ref "LED33") (pin "2") (pinfunction "K_2") (pintype "passive"))
      (node (ref "M1") (pin "1") (pinfunction "1_1") (pintype "passive"))
    )
    (net (code "35") (name "/RL34") (class "Default")
      (node (ref "D34") (pin "1") (pinfunction "A_1") (pintype "passive"))
      (node (ref "K34") (pin "4") (pinfunction "4_4") (pintype "passive"))
      (node (ref "LED34") (pin "2") (pinfunction "K_2") (pintype "passive"))
      (node (ref "M1") (pin "3") (pinfunction "3_3") (pintype "passive"))
    )
    (net (code "36") (name "/RL35") (class "Default")
      (node (ref "D35") (pin "1") (pinfunction "A_1") (pintype "passive"))
      (node (ref "K35") (pin "4") (pinfunction "4_4") (pintype "passive"))
      (node (ref "LED35") (pin "2") (pinfunction "K_2") (pintype "passive"))
      (node (ref "M1") (pin "5") (pinfunction "5_5") (pintype "passive"))
    )
    (net (code "37") (name "/RL36") (class "Default")
      (node (ref "D36") (pin "1") (pinfunction "A_1") (pintype "passive"))
      (node (ref "K36") (pin "4") (pinfunction "4_4") (pintype "passive"))
      (node (ref "LED36") (pin "2") (pinfunction "K_2") (pintype "passive"))
      (node (ref "M1") (pin "7") (pinfunction "7_7") (pintype "passive"))
    )
    (net (code "38") (name "/RL37") (class "Default")
      (node (ref "D37") (pin "1") (pinfunction "A_1") (pintype "passive"))
      (node (ref "K37") (pin "4") (pinfunction "4_4") (pintype "passive"))
      (node (ref "LED37") (pin "2") (pinfunction "K_2") (pintype "passive"))
      (node (ref "M1") (pin "9") (pinfunction "9_9") (pintype "passive"))
    )
    (net (code "39") (name "/RL38") (class "Default")
      (node (ref "D38") (pin "1") (pinfunction "A_1") (pintype "passive"))
      (node (ref "K38") (pin "4") (pinfunction "4_4") (pintype "passive"))
      (node (ref "LED38") (pin "2") (pinfunction "K_2") (pintype "passive"))
      (node (ref "M1") (pin "11") (pinfunction "11_11") (pintype "passive"))
    )
    (net (code "40") (name "/RL39") (class "Default")
      (node (ref "D39") (pin "1") (pinfunction "A_1") (pintype "passive"))
      (node (ref "K39") (pin "4") (pinfunction "4_4") (pintype "passive"))
      (node (ref "LED39") (pin "2") (pinfunction "K_2") (pintype "passive"))
      (node (ref "M1") (pin "13") (pinfunction "13_13") (pintype "passive"))
    )
    (net (code "41") (name "/RL40") (class "Default")
      (node (ref "D40") (pin "1") (pinfunction "A_1") (pintype "passive"))
      (node (ref "K40") (pin "4") (pinfunction "4_4") (pintype "passive"))
      (node (ref "LED40") (pin "2") (pinfunction "K_2") (pintype "passive"))
      (node (ref "M1") (pin "15") (pinfunction "15_15") (pintype "passive"))
    )
    (net (code "42") (name "GND") (class "Default")
      (node (ref "C1") (pin "2") (pinfunction "2_2") (pintype "passive"))
      (node (ref "DP2") (pin "2") (pinfunction "K_2") (pintype "passive"))
      (node (ref "Power") (pin "2") (pinfunction "2_2") (pintype "passive"))
      (node (ref "Q19") (pin "1") (pinfunction "E_1") (pintype "passive"))
    )
    (net (code "43") (name "Net-(D19-A)") (class "Default")
      (node (ref "D19") (pin "1") (pinfunction "A_1") (pintype "passive"))
      (node (ref "K19") (pin "4") (pinfunction "4_4") (pintype "passive"))
      (node (ref "LED19") (pin "2") (pinfunction "K_2") (pintype "passive"))
      (node (ref "Q19") (pin "2") (pinfunction "C_2") (pintype "passive"))
    )
    (net (code "44") (name "Net-(DP2-A)") (class "Default")
      (node (ref "DP2") (pin "1") (pinfunction "A_1") (pintype "passive"))
      (node (ref "Rp2") (pin "2") (pinfunction "2_2") (pintype "passive"))
    )
    (net (code "45") (name "Net-(K1-Pad1)") (class "Default")
      (node (ref "K1") (pin "1") (pinfunction "1_1") (pintype "passive"))
      (node (ref "RL1") (pin "1") (pinfunction "1_1") (pintype "passive"))
    )
    (net (code "46") (name "Net-(K1-Pad2)") (class "Default")
      (node (ref "K1") (pin "2") (pinfunction "2_2") (pintype "passive"))
      (node (ref "RL1") (pin "2") (pinfunction "2_2") (pintype "passive"))
    )
    (net (code "47") (name "Net-(K2-Pad1)") (class "Default")
      (node (ref "K2") (pin "1") (pinfunction "1_1") (pintype "passive"))
      (node (ref "RL2") (pin "1") (pinfunction "1_1") (pintype "passive"))
    )
    (net (code "48") (name "Net-(K2-Pad2)") (class "Default")
      (node (ref "K2") (pin "2") (pinfunction "2_2") (pintype "passive"))
      (node (ref "RL2") (pin "2") (pinfunction "2_2") (pintype "passive"))
    )
    (net (code "49") (name "Net-(K3-Pad1)") (class "Default")
      (node (ref "K3") (pin "1") (pinfunction "1_1") (pintype "passive"))
      (node (ref "RL3") (pin "1") (pinfunction "1_1") (pintype "passive"))
    )
    (net (code "50") (name "Net-(K3-Pad2)") (class "Default")
      (node (ref "K3") (pin "2") (pinfunction "2_2") (pintype "passive"))
      (node (ref "RL3") (pin "2") (pinfunction "2_2") (pintype "passive"))
    )
    (net (code "51") (name "Net-(K4-Pad1)") (class "Default")
      (node (ref "K4") (pin "1") (pinfunction "1_1") (pintype "passive"))
      (node (ref "RL4") (pin "1") (pinfunction "1_1") (pintype "passive"))
    )
    (net (code "52") (name "Net-(K4-Pad2)") (class "Default")
      (node (ref "K4") (pin "2") (pinfunction "2_2") (pintype "passive"))
      (node (ref "RL4") (pin "2") (pinfunction "2_2") (pintype "passive"))
    )
    (net (code "53") (name "Net-(K5-Pad1)") (class "Default")
      (node (ref "K5") (pin "1") (pinfunction "1_1") (pintype "passive"))
      (node (ref "RL5") (pin "1") (pinfunction "1_1") (pintype "passive"))
    )
    (net (code "54") (name "Net-(K5-Pad2)") (class "Default")
      (node (ref "K5") (pin "2") (pinfunction "2_2") (pintype "passive"))
      (node (ref "RL5") (pin "2") (pinfunction "2_2") (pintype "passive"))
    )
    (net (code "55") (name "Net-(K6-Pad1)") (class "Default")
      (node (ref "K6") (pin "1") (pinfunction "1_1") (pintype "passive"))
      (node (ref "RL6") (pin "1") (pinfunction "1_1") (pintype "passive"))
    )
    (net (code "56") (name "Net-(K6-Pad2)") (class "Default")
      (node (ref "K6") (pin "2") (pinfunction "2_2") (pintype "passive"))
      (node (ref "RL6") (pin "2") (pinfunction "2_2") (pintype "passive"))
    )
    (net (code "57") (name "Net-(K7-Pad1)") (class "Default")
      (node (ref "K7") (pin "1") (pinfunction "1_1") (pintype "passive"))
      (node (ref "RL7") (pin "1") (pinfunction "1_1") (pintype "passive"))
    )
    (net (code "58") (name "Net-(K7-Pad2)") (class "Default")
      (node (ref "K7") (pin "2") (pinfunction "2_2") (pintype "passive"))
      (node (ref "RL7") (pin "2") (pinfunction "2_2") (pintype "passive"))
    )
    (net (code "59") (name "Net-(K8-Pad1)") (class "Default")
      (node (ref "K8") (pin "1") (pinfunction "1_1") (pintype "passive"))
      (node (ref "RL8") (pin "1") (pinfunction "1_1") (pintype "passive"))
    )
    (net (code "60") (name "Net-(K8-Pad2)") (class "Default")
      (node (ref "K8") (pin "2") (pinfunction "2_2") (pintype "passive"))
      (node (ref "RL8") (pin "2") (pinfunction "2_2") (pintype "passive"))
    )
    (net (code "61") (name "Net-(K9-Pad1)") (class "Default")
      (node (ref "K9") (pin "1") (pinfunction "1_1") (pintype "passive"))
      (node (ref "RL9") (pin "1") (pinfunction "1_1") (pintype "passive"))
    )
    (net (code "62") (name "Net-(K9-Pad2)") (class "Default")
      (node (ref "K9") (pin "2") (pinfunction "2_2") (pintype "passive"))
      (node (ref "RL9") (pin "2") (pinfunction "2_2") (pintype "passive"))
    )
    (net (code "63") (name "Net-(K10-Pad1)") (class "Default")
      (node (ref "K10") (pin "1") (pinfunction "1_1") (pintype "passive"))
      (node (ref "RL10") (pin "1") (pinfunction "1_1") (pintype "passive"))
    )
    (net (code "64") (name "Net-(K10-Pad2)") (class "Default")
      (node (ref "K10") (pin "2") (pinfunction "2_2") (pintype "passive"))
      (node (ref "RL10") (pin "2") (pinfunction "2_2") (pintype "passive"))
    )
    (net (code "65") (name "Net-(K11-Pad1)") (class "Default")
      (node (ref "K11") (pin "1") (pinfunction "1_1") (pintype "passive"))
      (node (ref "RL11") (pin "1") (pinfunction "1_1") (pintype "passive"))
    )
    (net (code "66") (name "Net-(K11-Pad2)") (class "Default")
      (node (ref "K11") (pin "2") (pinfunction "2_2") (pintype "passive"))
      (node (ref "RL11") (pin "2") (pinfunction "2_2") (pintype "passive"))
    )
    (net (code "67") (name "Net-(K12-Pad1)") (class "Default")
      (node (ref "K12") (pin "1") (pinfunction "1_1") (pintype "passive"))
      (node (ref "RL12") (pin "1") (pinfunction "1_1") (pintype "passive"))
    )
    (net (code "68") (name "Net-(K12-Pad2)") (class "Default")
      (node (ref "K12") (pin "2") (pinfunction "2_2") (pintype "passive"))
      (node (ref "RL12") (pin "2") (pinfunction "2_2") (pintype "passive"))
    )
    (net (code "69") (name "Net-(K13-Pad1)") (class "Default")
      (node (ref "K13") (pin "1") (pinfunction "1_1") (pintype "passive"))
      (node (ref "RL13") (pin "1") (pinfunction "1_1") (pintype "passive"))
    )
    (net (code "70") (name "Net-(K13-Pad2)") (class "Default")
      (node (ref "K13") (pin "2") (pinfunction "2_2") (pintype "passive"))
      (node (ref "RL13") (pin "2") (pinfunction "2_2") (pintype "passive"))
    )
    (net (code "71") (name "Net-(K14-Pad1)") (class "Default")
      (node (ref "K14") (pin "1") (pinfunction "1_1") (pintype "passive"))
      (node (ref "RL14") (pin "1") (pinfunction "1_1") (pintype "passive"))
    )
    (net (code "72") (name "Net-(K14-Pad2)") (class "Default")
      (node (ref "K14") (pin "2") (pinfunction "2_2") (pintype "passive"))
      (node (ref "RL14") (pin "2") (pinfunction "2_2") (pintype "passive"))
    )
    (net (code "73") (name "Net-(K15-Pad1)") (class "Default")
      (node (ref "K15") (pin "1") (pinfunction "1_1") (pintype "passive"))
      (node (ref "RL15") (pin "1") (pinfunction "1_1") (pintype "passive"))
    )
    (net (code "74") (name "Net-(K15-Pad2)") (class "Default")
      (node (ref "K15") (pin "2") (pinfunction "2_2") (pintype "passive"))
      (node (ref "RL15") (pin "2") (pinfunction "2_2") (pintype "passive"))
    )
    (net (code "75") (name "Net-(K16-Pad1)") (class "Default")
      (node (ref "K16") (pin "1") (pinfunction "1_1") (pintype "passive"))
      (node (ref "RL16") (pin "1") (pinfunction "1_1") (pintype "passive"))
    )
    (net (code "76") (name "Net-(K16-Pad2)") (class "Default")
      (node (ref "K16") (pin "2") (pinfunction "2_2") (pintype "passive"))
      (node (ref "RL16") (pin "2") (pinfunction "2_2") (pintype "passive"))
    )
    (net (code "77") (name "Net-(K17-Pad1)") (class "Default")
      (node (ref "K17") (pin "1") (pinfunction "1_1") (pintype "passive"))
      (node (ref "RL17") (pin "1") (pinfunction "1_1") (pintype "passive"))
    )
    (net (code "78") (name "Net-(K17-Pad2)") (class "Default")
      (node (ref "K17") (pin "2") (pinfunction "2_2") (pintype "passive"))
      (node (ref "RL17") (pin "2") (pinfunction "2_2") (pintype "passive"))
    )
    (net (code "79") (name "Net-(K18-Pad1)") (class "Default")
      (node (ref "K18") (pin "1") (pinfunction "1_1") (pintype "passive"))
      (node (ref "RL18") (pin "1") (pinfunction "1_1") (pintype "passive"))
    )
    (net (code "80") (name "Net-(K18-Pad2)") (class "Default")
      (node (ref "K18") (pin "2") (pinfunction "2_2") (pintype "passive"))
      (node (ref "RL18") (pin "2") (pinfunction "2_2") (pintype "passive"))
    )
    (net (code "81") (name "Net-(K19-Pad1)") (class "Default")
      (node (ref "K19") (pin "1") (pinfunction "1_1") (pintype "passive"))
      (node (ref "RL19") (pin "1") (pinfunction "1_1") (pintype "passive"))
    )
    (net (code "82") (name "Net-(K19-Pad2)") (class "Default")
      (node (ref "K19") (pin "2") (pinfunction "2_2") (pintype "passive"))
      (node (ref "RL19") (pin "2") (pinfunction "2_2") (pintype "passive"))
    )
    (net (code "83") (name "Net-(K20-Pad1)") (class "Default")
      (node (ref "K20") (pin "1") (pinfunction "1_1") (pintype "passive"))
      (node (ref "RL20") (pin "1") (pinfunction "1_1") (pintype "passive"))
    )
    (net (code "84") (name "Net-(K20-Pad2)") (class "Default")
      (node (ref "K20") (pin "2") (pinfunction "2_2") (pintype "passive"))
      (node (ref "RL20") (pin "2") (pinfunction "2_2") (pintype "passive"))
    )
    (net (code "85") (name "Net-(K21-Pad1)") (class "Default")
      (node (ref "K21") (pin "1") (pinfunction "1_1") (pintype "passive"))
      (node (ref "RL21") (pin "1") (pinfunction "1_1") (pintype "passive"))
    )
    (net (code "86") (name "Net-(K21-Pad2)") (class "Default")
      (node (ref "K21") (pin "2") (pinfunction "2_2") (pintype "passive"))
      (node (ref "RL21") (pin "2") (pinfunction "2_2") (pintype "passive"))
    )
    (net (code "87") (name "Net-(K22-Pad1)") (class "Default")
      (node (ref "K22") (pin "1") (pinfunction "1_1") (pintype "passive"))
      (node (ref "RL22") (pin "1") (pinfunction "1_1") (pintype "passive"))
    )
    (net (code "88") (name "Net-(K22-Pad2)") (class "Default")
      (node (ref "K22") (pin "2") (pinfunction "2_2") (pintype "passive"))
      (node (ref "RL22") (pin "2") (pinfunction "2_2") (pintype "passive"))
    )
    (net (code "89") (name "Net-(K23-Pad1)") (class "Default")
      (node (ref "K23") (pin "1") (pinfunction "1_1") (pintype "passive"))
      (node (ref "RL23") (pin "1") (pinfunction "1_1") (pintype "passive"))
    )
    (net (code "90") (name "Net-(K23-Pad2)") (class "Default")
      (node (ref "K23") (pin "2") (pinfunction "2_2") (pintype "passive"))
      (node (ref "RL23") (pin "2") (pinfunction "2_2") (pintype "passive"))
    )
    (net (code "91") (name "Net-(K24-Pad1)") (class "Default")
      (node (ref "K24") (pin "1") (pinfunction "1_1") (pintype "passive"))
      (node (ref "RL24") (pin "1") (pinfunction "1_1") (pintype "passive"))
    )
    (net (code "92") (name "Net-(K24-Pad2)") (class "Default")
      (node (ref "K24") (pin "2") (pinfunction "2_2") (pintype "passive"))
      (node (ref "RL24") (pin "2") (pinfunction "2_2") (pintype "passive"))
    )
    (net (code "93") (name "Net-(K25-Pad1)") (class "Default")
      (node (ref "K25") (pin "1") (pinfunction "1_1") (pintype "passive"))
      (node (ref "RL25") (pin "1") (pinfunction "1_1") (pintype "passive"))
    )
    (net (code "94") (name "Net-(K25-Pad2)") (class "Default")
      (node (ref "K25") (pin "2") (pinfunction "2_2") (pintype "passive"))
      (node (ref "RL25") (pin "2") (pinfunction "2_2") (pintype "passive"))
    )
    (net (code "95") (name "Net-(K26-Pad1)") (class "Default")
      (node (ref "K26") (pin "1") (pinfunction "1_1") (pintype "passive"))
      (node (ref "RL26") (pin "1") (pinfunction "1_1") (pintype "passive"))
    )
    (net (code "96") (name "Net-(K26-Pad2)") (class "Default")
      (node (ref "K26") (pin "2") (pinfunction "2_2") (pintype "passive"))
      (node (ref "RL26") (pin "2") (pinfunction "2_2") (pintype "passive"))
    )
    (net (code "97") (name "Net-(K27-Pad1)") (class "Default")
      (node (ref "K27") (pin "1") (pinfunction "1_1") (pintype "passive"))
      (node (ref "RL27") (pin "1") (pinfunction "1_1") (pintype "passive"))
    )
    (net (code "98") (name "Net-(K27-Pad2)") (class "Default")
      (node (ref "K27") (pin "2") (pinfunction "2_2") (pintype "passive"))
      (node (ref "RL27") (pin "2") (pinfunction "2_2") (pintype "passive"))
    )
    (net (code "99") (name "Net-(K28-Pad1)") (class "Default")
      (node (ref "K28") (pin "1") (pinfunction "1_1") (pintype "passive"))
      (node (ref "RL28") (pin "1") (pinfunction "1_1") (pintype "passive"))
    )
    (net (code "100") (name "Net-(K28-Pad2)") (class "Default")
      (node (ref "K28") (pin "2") (pinfunction "2_2") (pintype "passive"))
      (node (ref "RL28") (pin "2") (pinfunction "2_2") (pintype "passive"))
    )
    (net (code "101") (name "Net-(K29-Pad1)") (class "Default")
      (node (ref "K29") (pin "1") (pinfunction "1_1") (pintype "passive"))
      (node (ref "RL29") (pin "1") (pinfunction "1_1") (pintype "passive"))
    )
    (net (code "102") (name "Net-(K29-Pad2)") (class "Default")
      (node (ref "K29") (pin "2") (pinfunction "2_2") (pintype "passive"))
      (node (ref "RL29") (pin "2") (pinfunction "2_2") (pintype "passive"))
    )
    (net (code "103") (name "Net-(K30-Pad1)") (class "Default")
      (node (ref "K30") (pin "1") (pinfunction "1_1") (pintype "passive"))
      (node (ref "RL30") (pin "1") (pinfunction "1_1") (pintype "passive"))
    )
    (net (code "104") (name "Net-(K30-Pad2)") (class "Default")
      (node (ref "K30") (pin "2") (pinfunction "2_2") (pintype "passive"))
      (node (ref "RL30") (pin "2") (pinfunction "2_2") (pintype "passive"))
    )
    (net (code "105") (name "Net-(K31-Pad1)") (class "Default")
      (node (ref "K31") (pin "1") (pinfunction "1_1") (pintype "passive"))
      (node (ref "RL31") (pin "1") (pinfunction "1_1") (pintype "passive"))
    )
    (net (code "106") (name "Net-(K31-Pad2)") (class "Default")
      (node (ref "K31") (pin "2") (pinfunction "2_2") (pintype "passive"))
      (node (ref "RL31") (pin "2") (pinfunction "2_2") (pintype "passive"))
    )
    (net (code "107") (name "Net-(K32-Pad1)") (class "Default")
      (node (ref "K32") (pin "1") (pinfunction "1_1") (pintype "passive"))
      (node (ref "RL32") (pin "1") (pinfunction "1_1") (pintype "passive"))
    )
    (net (code "108") (name "Net-(K32-Pad2)") (class "Default")
      (node (ref "K32") (pin "2") (pinfunction "2_2") (pintype "passive"))
      (node (ref "RL32") (pin "2") (pinfunction "2_2") (pintype "passive"))
    )
    (net (code "109") (name "Net-(K33-Pad1)") (class "Default")
      (node (ref "K33") (pin "1") (pinfunction "1_1") (pintype "passive"))
      (node (ref "RL33") (pin "1") (pinfunction "1_1") (pintype "passive"))
    )
    (net (code "110") (name "Net-(K33-Pad2)") (class "Default")
      (node (ref "K33") (pin "2") (pinfunction "2_2") (pintype "passive"))
      (node (ref "RL33") (pin "2") (pinfunction "2_2") (pintype "passive"))
    )
    (net (code "111") (name "Net-(K34-Pad1)") (class "Default")
      (node (ref "K34") (pin "1") (pinfunction "1_1") (pintype "passive"))
      (node (ref "RL34") (pin "1") (pinfunction "1_1") (pintype "passive"))
    )
    (net (code "112") (name "Net-(K34-Pad2)") (class "Default")
      (node (ref "K34") (pin "2") (pinfunction "2_2") (pintype "passive"))
      (node (ref "RL34") (pin "2") (pinfunction "2_2") (pintype "passive"))
    )
    (net (code "113") (name "Net-(K35-Pad1)") (class "Default")
      (node (ref "K35") (pin "1") (pinfunction "1_1") (pintype "passive"))
      (node (ref "RL35") (pin "1") (pinfunction "1_1") (pintype "passive"))
    )
    (net (code "114") (name "Net-(K35-Pad2)") (class "Default")
      (node (ref "K35") (pin "2") (pinfunction "2_2") (pintype "passive"))
      (node (ref "RL35") (pin "2") (pinfunction "2_2") (pintype "passive"))
    )
    (net (code "115") (name "Net-(K36-Pad1)") (class "Default")
      (node (ref "K36") (pin "1") (pinfunction "1_1") (pintype "passive"))
      (node (ref "RL36") (pin "1") (pinfunction "1_1") (pintype "passive"))
    )
    (net (code "116") (name "Net-(K36-Pad2)") (class "Default")
      (node (ref "K36") (pin "2") (pinfunction "2_2") (pintype "passive"))
      (node (ref "RL36") (pin "2") (pinfunction "2_2") (pintype "passive"))
    )
    (net (code "117") (name "Net-(K37-Pad1)") (class "Default")
      (node (ref "K37") (pin "1") (pinfunction "1_1") (pintype "passive"))
      (node (ref "RL37") (pin "1") (pinfunction "1_1") (pintype "passive"))
    )
    (net (code "118") (name "Net-(K37-Pad2)") (class "Default")
      (node (ref "K37") (pin "2") (pinfunction "2_2") (pintype "passive"))
      (node (ref "RL37") (pin "2") (pinfunction "2_2") (pintype "passive"))
    )
    (net (code "119") (name "Net-(K38-Pad1)") (class "Default")
      (node (ref "K38") (pin "1") (pinfunction "1_1") (pintype "passive"))
      (node (ref "RL38") (pin "1") (pinfunction "1_1") (pintype "passive"))
    )
    (net (code "120") (name "Net-(K38-Pad2)") (class "Default")
      (node (ref "K38") (pin "2") (pinfunction "2_2") (pintype "passive"))
      (node (ref "RL38") (pin "2") (pinfunction "2_2") (pintype "passive"))
    )
    (net (code "121") (name "Net-(K39-Pad1)") (class "Default")
      (node (ref "K39") (pin "1") (pinfunction "1_1") (pintype "passive"))
      (node (ref "RL39") (pin "1") (pinfunction "1_1") (pintype "passive"))
    )
    (net (code "122") (name "Net-(K39-Pad2)") (class "Default")
      (node (ref "K39") (pin "2") (pinfunction "2_2") (pintype "passive"))
      (node (ref "RL39") (pin "2") (pinfunction "2_2") (pintype "passive"))
    )
    (net (code "123") (name "Net-(K40-Pad1)") (class "Default")
      (node (ref "K40") (pin "1") (pinfunction "1_1") (pintype "passive"))
      (node (ref "RL40") (pin "1") (pinfunction "1_1") (pintype "passive"))
    )
    (net (code "124") (name "Net-(K40-Pad2)") (class "Default")
      (node (ref "K40") (pin "2") (pinfunction "2_2") (pintype "passive"))
      (node (ref "RL40") (pin "2") (pinfunction "2_2") (pintype "passive"))
    )
    (net (code "125") (name "Net-(LED1-A)") (class "Default")
      (node (ref "LED1") (pin "1") (pinfunction "A_1") (pintype "passive"))
      (node (ref "R1") (pin "2") (pinfunction "2_2") (pintype "passive"))
    )
    (net (code "126") (name "Net-(LED2-A)") (class "Default")
      (node (ref "LED2") (pin "1") (pinfunction "A_1") (pintype "passive"))
      (node (ref "R2") (pin "2") (pinfunction "2_2") (pintype "passive"))
    )
    (net (code "127") (name "Net-(LED3-A)") (class "Default")
      (node (ref "LED3") (pin "1") (pinfunction "A_1") (pintype "passive"))
      (node (ref "R3") (pin "2") (pinfunction "2_2") (pintype "passive"))
    )
    (net (code "128") (name "Net-(LED4-A)") (class "Default")
      (node (ref "LED4") (pin "1") (pinfunction "A_1") (pintype "passive"))
      (node (ref "R4") (pin "2") (pinfunction "2_2") (pintype "passive"))
    )
    (net (code "129") (name "Net-(LED5-A)") (class "Default")
      (node (ref "LED5") (pin "1") (pinfunction "A_1") (pintype "passive"))
      (node (ref "R5") (pin "2") (pinfunction "2_2") (pintype "passive"))
    )
    (net (code "130") (name "Net-(LED6-A)") (class "Default")
      (node (ref "LED6") (pin "1") (pinfunction "A_1") (pintype "passive"))
      (node (ref "R6") (pin "2") (pinfunction "2_2") (pintype "passive"))
    )
    (net (code "131") (name "Net-(LED7-A)") (class "Default")
      (node (ref "LED7") (pin "1") (pinfunction "A_1") (pintype "passive"))
      (node (ref "R7") (pin "2") (pinfunction "2_2") (pintype "passive"))
    )
    (net (code "132") (name "Net-(LED8-A)") (class "Default")
      (node (ref "LED8") (pin "1") (pinfunction "A_1") (pintype "passive"))
      (node (ref "R8") (pin "2") (pinfunction "2_2") (pintype "passive"))
    )
    (net (code "133") (name "Net-(LED9-A)") (class "Default")
      (node (ref "LED9") (pin "1") (pinfunction "A_1") (pintype "passive"))
      (node (ref "R9") (pin "2") (pinfunction "2_2") (pintype "passive"))
    )
    (net (code "134") (name "Net-(LED10-A)") (class "Default")
      (node (ref "LED10") (pin "1") (pinfunction "A_1") (pintype "passive"))
      (node (ref "R10") (pin "2") (pinfunction "2_2") (pintype "passive"))
    )
    (net (code "135") (name "Net-(LED11-A)") (class "Default")
      (node (ref "LED11") (pin "1") (pinfunction "A_1") (pintype "passive"))
      (node (ref "R11") (pin "2") (pinfunction "2_2") (pintype "passive"))
    )
    (net (code "136") (name "Net-(LED12-A)") (class "Default")
      (node (ref "LED12") (pin "1") (pinfunction "A_1") (pintype "passive"))
      (node (ref "R12") (pin "2") (pinfunction "2_2") (pintype "passive"))
    )
    (net (code "137") (name "Net-(LED13-A)") (class "Default")
      (node (ref "LED13") (pin "1") (pinfunction "A_1") (pintype "passive"))
      (node (ref "R13") (pin "2") (pinfunction "2_2") (pintype "passive"))
    )
    (net (code "138") (name "Net-(LED14-A)") (class "Default")
      (node (ref "LED14") (pin "1") (pinfunction "A_1") (pintype "passive"))
      (node (ref "R14") (pin "2") (pinfunction "2_2") (pintype "passive"))
    )
    (net (code "139") (name "Net-(LED15-A)") (class "Default")
      (node (ref "LED15") (pin "1") (pinfunction "A_1") (pintype "passive"))
      (node (ref "R15") (pin "2") (pinfunction "2_2") (pintype "passive"))
    )
    (net (code "140") (name "Net-(LED16-A)") (class "Default")
      (node (ref "LED16") (pin "1") (pinfunction "A_1") (pintype "passive"))
      (node (ref "R16") (pin "2") (pinfunction "2_2") (pintype "passive"))
    )
    (net (code "141") (name "Net-(LED17-A)") (class "Default")
      (node (ref "LED17") (pin "1") (pinfunction "A_1") (pintype "passive"))
      (node (ref "R17") (pin "2") (pinfunction "2_2") (pintype "passive"))
    )
    (net (code "142") (name "Net-(LED18-A)") (class "Default")
      (node (ref "LED18") (pin "1") (pinfunction "A_1") (pintype "passive"))
      (node (ref "R18") (pin "2") (pinfunction "2_2") (pintype "passive"))
    )
    (net (code "143") (name "Net-(LED19-A)") (class "Default")
      (node (ref "LED19") (pin "1") (pinfunction "A_1") (pintype "passive"))
      (node (ref "R19") (pin "2") (pinfunction "2_2") (pintype "passive"))
    )
    (net (code "144") (name "Net-(LED20-A)") (class "Default")
      (node (ref "LED20") (pin "1") (pinfunction "A_1") (pintype "passive"))
      (node (ref "R20") (pin "2") (pinfunction "2_2") (pintype "passive"))
    )
    (net (code "145") (name "Net-(LED21-A)") (class "Default")
      (node (ref "LED21") (pin "1") (pinfunction "A_1") (pintype "passive"))
      (node (ref "R21") (pin "2") (pinfunction "2_2") (pintype "passive"))
    )
    (net (code "146") (name "Net-(LED22-A)") (class "Default")
      (node (ref "LED22") (pin "1") (pinfunction "A_1") (pintype "passive"))
      (node (ref "R22") (pin "2") (pinfunction "2_2") (pintype "passive"))
    )
    (net (code "147") (name "Net-(LED23-A)") (class "Default")
      (node (ref "LED23") (pin "1") (pinfunction "A_1") (pintype "passive"))
      (node (ref "R23") (pin "2") (pinfunction "2_2") (pintype "passive"))
    )
    (net (code "148") (name "Net-(LED24-A)") (class "Default")
      (node (ref "LED24") (pin "1") (pinfunction "A_1") (pintype "passive"))
      (node (ref "R24") (pin "2") (pinfunction "2_2") (pintype "passive"))
    )
    (net (code "149") (name "Net-(LED25-A)") (class "Default")
      (node (ref "LED25") (pin "1") (pinfunction "A_1") (pintype "passive"))
      (node (ref "R25") (pin "2") (pinfunction "2_2") (pintype "passive"))
    )
    (net (code "150") (name "Net-(LED26-A)") (class "Default")
      (node (ref "LED26") (pin "1") (pinfunction "A_1") (pintype "passive"))
      (node (ref "R26") (pin "2") (pinfunction "2_2") (pintype "passive"))
    )
    (net (code "151") (name "Net-(LED27-A)") (class "Default")
      (node (ref "LED27") (pin "1") (pinfunction "A_1") (pintype "passive"))
      (node (ref "R27") (pin "2") (pinfunction "2_2") (pintype "passive"))
    )
    (net (code "152") (name "Net-(LED28-A)") (class "Default")
      (node (ref "LED28") (pin "1") (pinfunction "A_1") (pintype "passive"))
      (node (ref "R28") (pin "2") (pinfunction "2_2") (pintype "passive"))
    )
    (net (code "153") (name "Net-(LED29-A)") (class "Default")
      (node (ref "LED29") (pin "1") (pinfunction "A_1") (pintype "passive"))
      (node (ref "R29") (pin "2") (pinfunction "2_2") (pintype "passive"))
    )
    (net (code "154") (name "Net-(LED30-A)") (class "Default")
      (node (ref "LED30") (pin "1") (pinfunction "A_1") (pintype "passive"))
      (node (ref "R30") (pin "2") (pinfunction "2_2") (pintype "passive"))
    )
    (net (code "155") (name "Net-(LED31-A)") (class "Default")
      (node (ref "LED31") (pin "1") (pinfunction "A_1") (pintype "passive"))
      (node (ref "R31") (pin "2") (pinfunction "2_2") (pintype "passive"))
    )
    (net (code "156") (name "Net-(LED32-A)") (class "Default")
      (node (ref "LED32") (pin "1") (pinfunction "A_1") (pintype "passive"))
      (node (ref "R32") (pin "2") (pinfunction "2_2") (pintype "passive"))
    )
    (net (code "157") (name "Net-(LED33-A)") (class "Default")
      (node (ref "LED33") (pin "1") (pinfunction "A_1") (pintype "passive"))
      (node (ref "R33") (pin "2") (pinfunction "2_2") (pintype "passive"))
    )
    (net (code "158") (name "Net-(LED34-A)") (class "Default")
      (node (ref "LED34") (pin "1") (pinfunction "A_1") (pintype "passive"))
      (node (ref "R34") (pin "2") (pinfunction "2_2") (pintype "passive"))
    )
    (net (code "159") (name "Net-(LED35-A)") (class "Default")
      (node (ref "LED35") (pin "1") (pinfunction "A_1") (pintype "passive"))
      (node (ref "R35") (pin "2") (pinfunction "2_2") (pintype "passive"))
    )
    (net (code "160") (name "Net-(LED36-A)") (class "Default")
      (node (ref "LED36") (pin "1") (pinfunction "A_1") (pintype "passive"))
      (node (ref "R36") (pin "2") (pinfunction "2_2") (pintype "passive"))
    )
    (net (code "161") (name "Net-(LED37-A)") (class "Default")
      (node (ref "LED37") (pin "1") (pinfunction "A_1") (pintype "passive"))
      (node (ref "R37") (pin "2") (pinfunction "2_2") (pintype "passive"))
    )
    (net (code "162") (name "Net-(LED38-A)") (class "Default")
      (node (ref "LED38") (pin "1") (pinfunction "A_1") (pintype "passive"))
      (node (ref "R38") (pin "2") (pinfunction "2_2") (pintype "passive"))
    )
    (net (code "163") (name "Net-(LED39-A)") (class "Default")
      (node (ref "LED39") (pin "1") (pinfunction "A_1") (pintype "passive"))
      (node (ref "R39") (pin "2") (pinfunction "2_2") (pintype "passive"))
    )
    (net (code "164") (name "Net-(LED40-A)") (class "Default")
      (node (ref "LED40") (pin "1") (pinfunction "A_1") (pintype "passive"))
      (node (ref "R40") (pin "2") (pinfunction "2_2") (pintype "passive"))
    )
  )
)
